# Vocodec_rev2_2.net
KiCad netlist of a schematic drawn in EAGLE
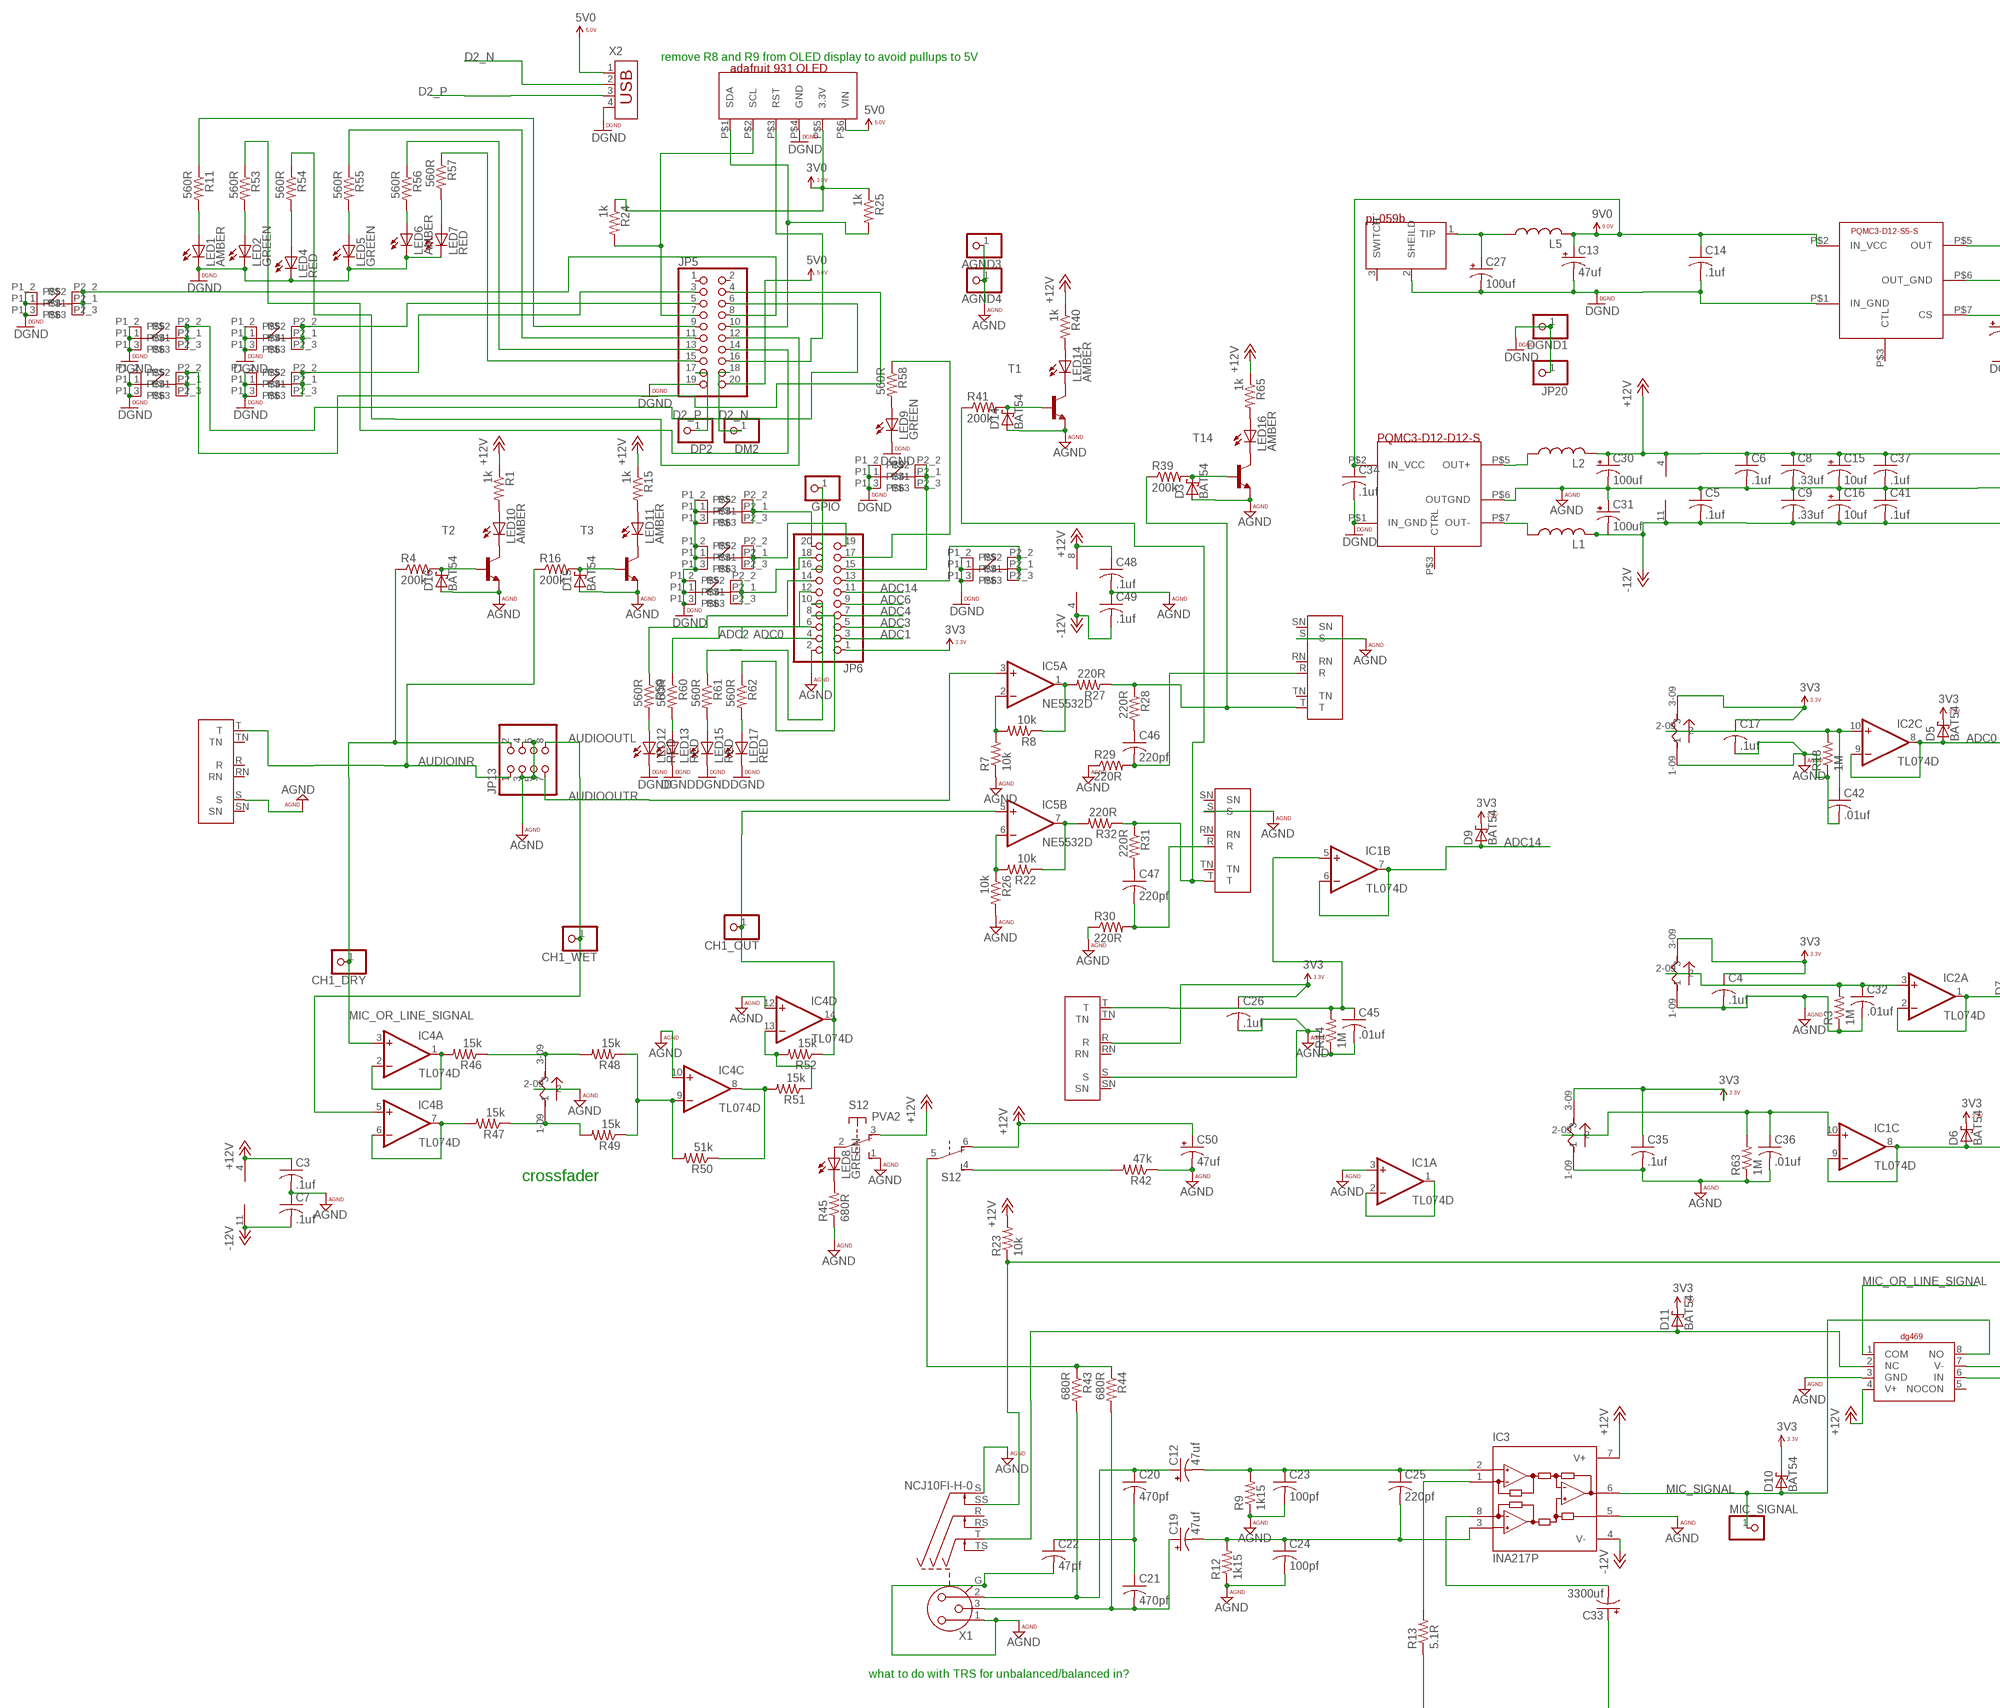
[diagram p0: schematic, sheet 1, part 1 of 3]
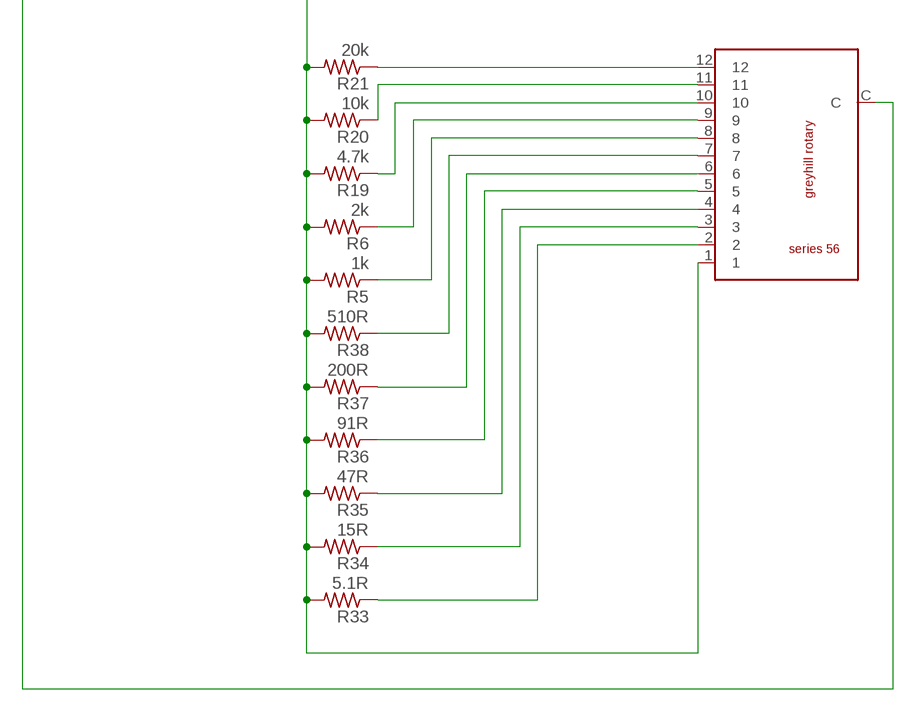
[diagram p1: schematic, sheet 1, part 2 of 3]
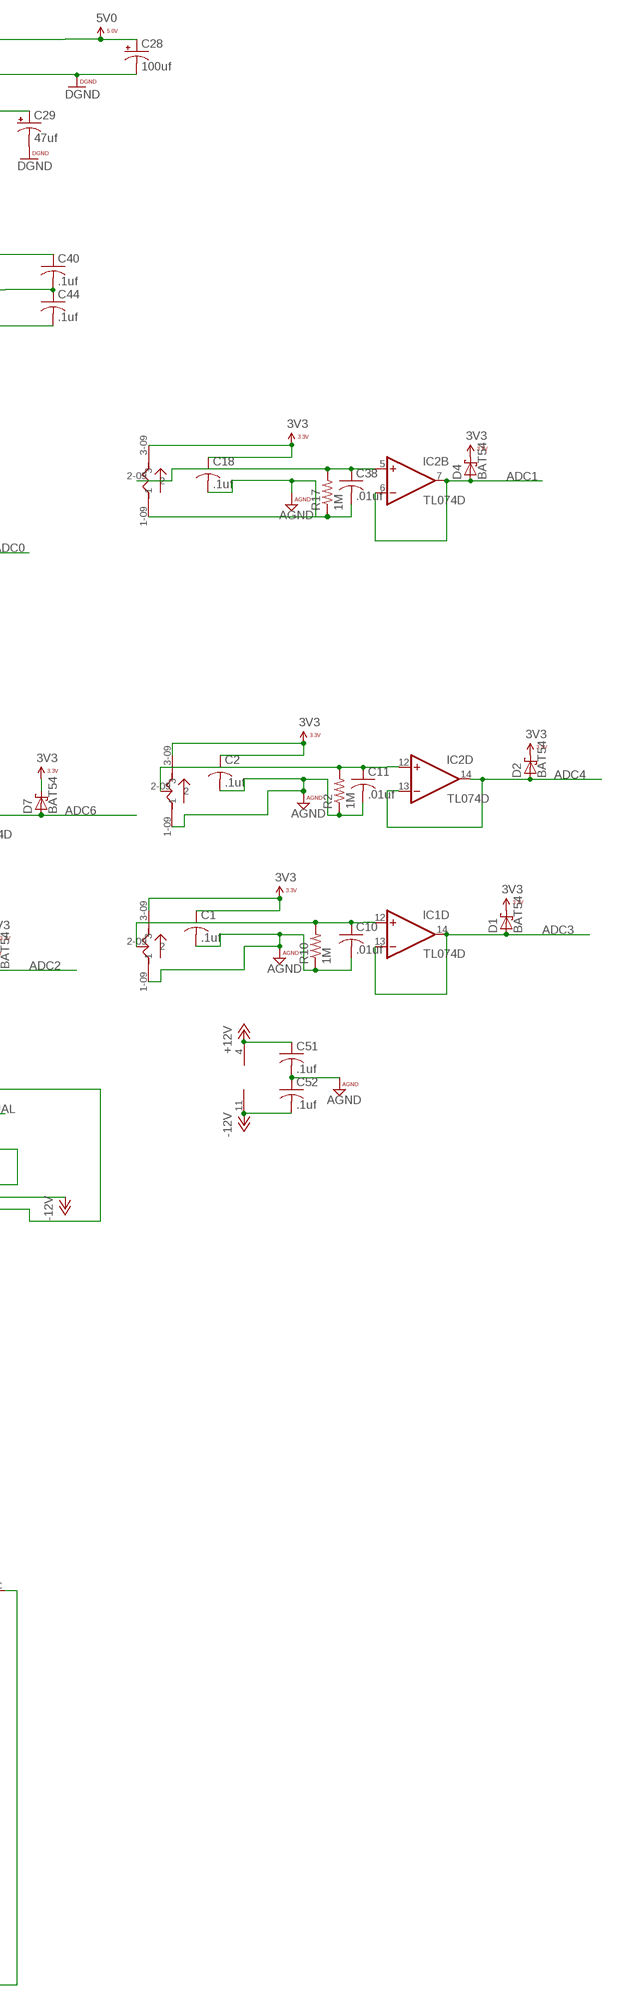
[diagram p2: schematic, sheet 1, part 3 of 3]

(export (version "E")
  (design (tool "Eeschema 10.0.6"))
  (components
    (comp (ref "AGND3")
      (value "PINHD-1X1")
      (footprint "eagle-import:1X01")
      (fields (field (name "PARTNO") "*DNP"))
      (libsource (lib "eagle-import") (part "PINHD-1X1"))
    )
    (comp (ref "AGND4")
      (value "PINHD-1X1")
      (footprint "eagle-import:1X01")
      (fields (field (name "PARTNO") "*DNP"))
      (libsource (lib "eagle-import") (part "PINHD-1X1"))
    )
    (comp (ref "C1")
      (value ".1uf")
      (footprint "eagle-import:C0603")
      (fields (field (name "PARTNO") "CC0603KRX7R8BB104"))
      (libsource (lib "eagle-import") (part "C-USC0603"))
    )
    (comp (ref "C2")
      (value ".1uf")
      (footprint "eagle-import:C0603")
      (fields (field (name "PARTNO") "CC0603KRX7R8BB104"))
      (libsource (lib "eagle-import") (part "C-USC0603"))
    )
    (comp (ref "C3")
      (value ".1uf")
      (footprint "eagle-import:C0603")
      (fields (field (name "PARTNO") "CC0603KRX7R8BB104"))
      (libsource (lib "eagle-import") (part "C-USC0603"))
    )
    (comp (ref "C4")
      (value ".1uf")
      (footprint "eagle-import:C0603")
      (fields (field (name "PARTNO") "CC0603KRX7R8BB104"))
      (libsource (lib "eagle-import") (part "C-USC0603"))
    )
    (comp (ref "C5")
      (value ".1uf")
      (footprint "eagle-import:C0603")
      (fields (field (name "PARTNO") "CC0603KRX7R8BB104"))
      (libsource (lib "eagle-import") (part "C-USC0603"))
    )
    (comp (ref "C6")
      (value ".1uf")
      (footprint "eagle-import:C0603")
      (fields (field (name "PARTNO") "CC0603KRX7R8BB104"))
      (libsource (lib "eagle-import") (part "C-USC0603"))
    )
    (comp (ref "C7")
      (value ".1uf")
      (footprint "eagle-import:C0603")
      (fields (field (name "PARTNO") "CC0603KRX7R8BB104"))
      (libsource (lib "eagle-import") (part "C-USC0603"))
    )
    (comp (ref "C8")
      (value ".33uf")
      (footprint "eagle-import:C0603")
      (fields (field (name "PARTNO") "C1608X7R1H334K080AC"))
      (libsource (lib "eagle-import") (part "C-USC0603"))
    )
    (comp (ref "C9")
      (value ".33uf")
      (footprint "eagle-import:C0603")
      (fields (field (name "PARTNO") "C1608X7R1H334K080AC"))
      (libsource (lib "eagle-import") (part "C-USC0603"))
    )
    (comp (ref "C10")
      (value ".01uf")
      (footprint "eagle-import:C0603")
      (fields (field (name "PARTNO") "CC0603KRX7R8BB103"))
      (libsource (lib "eagle-import") (part "C-USC0603"))
    )
    (comp (ref "C11")
      (value ".01uf")
      (footprint "eagle-import:C0603")
      (fields (field (name "PARTNO") "CC0603KRX7R8BB103"))
      (libsource (lib "eagle-import") (part "C-USC0603"))
    )
    (comp (ref "C12")
      (value "47uf")
      (footprint "eagle-import:PANASONIC_E")
      (fields (field (name "PARTNO") "EEE-1VA470AP"))
      (libsource (lib "eagle-import") (part "CPOL-USE"))
    )
    (comp (ref "C13")
      (value "47uf")
      (footprint "eagle-import:PANASONIC_E")
      (fields (field (name "PARTNO") "EEE-1VA470AP"))
      (libsource (lib "eagle-import") (part "CPOL-USE"))
    )
    (comp (ref "C14")
      (value ".1uf")
      (footprint "eagle-import:C0603")
      (fields (field (name "PARTNO") "CC0603KRX7R8BB104"))
      (libsource (lib "eagle-import") (part "C-USC0603"))
    )
    (comp (ref "C15")
      (value "10uf")
      (footprint "eagle-import:PANASONIC_C")
      (fields (field (name "PARTNO") "EEE-1VA100AR"))
      (libsource (lib "eagle-import") (part "CPOL-USC"))
    )
    (comp (ref "C16")
      (value "10uf")
      (footprint "eagle-import:PANASONIC_C")
      (fields (field (name "PARTNO") "EEE-1VA100AR"))
      (libsource (lib "eagle-import") (part "CPOL-USC"))
    )
    (comp (ref "C17")
      (value ".1uf")
      (footprint "eagle-import:C0603")
      (fields (field (name "PARTNO") "CC0603KRX7R8BB104"))
      (libsource (lib "eagle-import") (part "C-USC0603"))
    )
    (comp (ref "C18")
      (value ".1uf")
      (footprint "eagle-import:C0603")
      (fields (field (name "PARTNO") "CC0603KRX7R8BB104"))
      (libsource (lib "eagle-import") (part "C-USC0603"))
    )
    (comp (ref "C19")
      (value "47uf")
      (footprint "eagle-import:PANASONIC_E")
      (fields (field (name "PARTNO") "EEE-1VA470AP"))
      (libsource (lib "eagle-import") (part "CPOL-USE"))
    )
    (comp (ref "C20")
      (value "470pf")
      (footprint "eagle-import:C0603")
      (fields (field (name "PARTNO") "CC0603JRNPO9BN471"))
      (libsource (lib "eagle-import") (part "C-USC0603"))
    )
    (comp (ref "C21")
      (value "470pf")
      (footprint "eagle-import:C0603")
      (fields (field (name "PARTNO") "CC0603JRNPO9BN471"))
      (libsource (lib "eagle-import") (part "C-USC0603"))
    )
    (comp (ref "C22")
      (value "47pf")
      (footprint "eagle-import:C0603")
      (fields (field (name "PARTNO") "C0603C470J5GACTU"))
      (libsource (lib "eagle-import") (part "C-USC0603"))
    )
    (comp (ref "C23")
      (value "100pf")
      (footprint "eagle-import:C0603")
      (fields (field (name "PARTNO") "C0603C101J3GACTU"))
      (libsource (lib "eagle-import") (part "C-USC0603"))
    )
    (comp (ref "C24")
      (value "100pf")
      (footprint "eagle-import:C0603")
      (fields (field (name "PARTNO") "C0603C101J3GACTU"))
      (libsource (lib "eagle-import") (part "C-USC0603"))
    )
    (comp (ref "C25")
      (value "220pf")
      (footprint "eagle-import:C0603")
      (fields (field (name "PARTNO") "CC0603JRNPO9BN221"))
      (libsource (lib "eagle-import") (part "C-USC0603"))
    )
    (comp (ref "C26")
      (value ".1uf")
      (footprint "eagle-import:C0603")
      (fields (field (name "PARTNO") "CC0603KRX7R8BB104"))
      (libsource (lib "eagle-import") (part "C-USC0603"))
    )
    (comp (ref "C27")
      (value "100uf")
      (footprint "eagle-import:PANASONIC_F")
      (fields (field (name "PARTNO") "EEE-1EA101P"))
      (libsource (lib "eagle-import") (part "CPOL-USF"))
    )
    (comp (ref "C28")
      (value "100uf")
      (footprint "eagle-import:PANASONIC_F")
      (fields (field (name "PARTNO") "EEE-1EA101P"))
      (libsource (lib "eagle-import") (part "CPOL-USF"))
    )
    (comp (ref "C29")
      (value "47uf")
      (footprint "eagle-import:PANASONIC_E")
      (fields (field (name "PARTNO") "EEE-1VA470AP"))
      (libsource (lib "eagle-import") (part "CPOL-USE"))
    )
    (comp (ref "C30")
      (value "100uf")
      (footprint "eagle-import:PANASONIC_F")
      (fields (field (name "PARTNO") "EEE-1EA101P"))
      (libsource (lib "eagle-import") (part "CPOL-USF"))
    )
    (comp (ref "C31")
      (value "100uf")
      (footprint "eagle-import:PANASONIC_F")
      (fields (field (name "PARTNO") "EEE-1EA101P"))
      (libsource (lib "eagle-import") (part "CPOL-USF"))
    )
    (comp (ref "C32")
      (value ".01uf")
      (footprint "eagle-import:C0603")
      (fields (field (name "PARTNO") "CC0603KRX7R8BB103"))
      (libsource (lib "eagle-import") (part "C-USC0603"))
    )
    (comp (ref "C33")
      (value "3300uf")
      (footprint "eagle-import:E5-13")
      (fields (field (name "PARTNO") "EEU-FR1A332"))
      (libsource (lib "eagle-import") (part "CPOL-USE5-13"))
    )
    (comp (ref "C34")
      (value ".1uf")
      (footprint "eagle-import:C0603")
      (fields (field (name "PARTNO") "CC0603KRX7R8BB104"))
      (libsource (lib "eagle-import") (part "C-USC0603"))
    )
    (comp (ref "C35")
      (value ".1uf")
      (footprint "eagle-import:C0603")
      (fields (field (name "PARTNO") "CC0603KRX7R8BB104"))
      (libsource (lib "eagle-import") (part "C-USC0603"))
    )
    (comp (ref "C36")
      (value ".01uf")
      (footprint "eagle-import:C0603")
      (fields (field (name "PARTNO") "CC0603KRX7R8BB103"))
      (libsource (lib "eagle-import") (part "C-USC0603"))
    )
    (comp (ref "C37")
      (value ".1uf")
      (footprint "eagle-import:C0603")
      (fields (field (name "PARTNO") "CC0603KRX7R8BB104"))
      (libsource (lib "eagle-import") (part "C-USC0603"))
    )
    (comp (ref "C38")
      (value ".01uf")
      (footprint "eagle-import:C0603")
      (fields (field (name "PARTNO") "CC0603KRX7R8BB103"))
      (libsource (lib "eagle-import") (part "C-USC0603"))
    )
    (comp (ref "C40")
      (value ".1uf")
      (footprint "eagle-import:C0603")
      (fields (field (name "PARTNO") "CC0603KRX7R8BB104"))
      (libsource (lib "eagle-import") (part "C-USC0603"))
    )
    (comp (ref "C41")
      (value ".1uf")
      (footprint "eagle-import:C0603")
      (fields (field (name "PARTNO") "CC0603KRX7R8BB104"))
      (libsource (lib "eagle-import") (part "C-USC0603"))
    )
    (comp (ref "C42")
      (value ".01uf")
      (footprint "eagle-import:C0603")
      (fields (field (name "PARTNO") "CC0603KRX7R8BB103"))
      (libsource (lib "eagle-import") (part "C-USC0603"))
    )
    (comp (ref "C44")
      (value ".1uf")
      (footprint "eagle-import:C0603")
      (fields (field (name "PARTNO") "CC0603KRX7R8BB104"))
      (libsource (lib "eagle-import") (part "C-USC0603"))
    )
    (comp (ref "C45")
      (value ".01uf")
      (footprint "eagle-import:C0603")
      (fields (field (name "PARTNO") "CC0603KRX7R8BB103"))
      (libsource (lib "eagle-import") (part "C-USC0603"))
    )
    (comp (ref "C46")
      (value "220pf")
      (footprint "eagle-import:C0603")
      (fields (field (name "PARTNO") "CC0603JRNPO9BN221"))
      (libsource (lib "eagle-import") (part "C-USC0603"))
    )
    (comp (ref "C47")
      (value "220pf")
      (footprint "eagle-import:C0603")
      (fields (field (name "PARTNO") "CC0603JRNPO9BN221"))
      (libsource (lib "eagle-import") (part "C-USC0603"))
    )
    (comp (ref "C48")
      (value ".1uf")
      (footprint "eagle-import:C0603")
      (fields (field (name "PARTNO") "CC0603KRX7R8BB104"))
      (libsource (lib "eagle-import") (part "C-USC0603"))
    )
    (comp (ref "C49")
      (value ".1uf")
      (footprint "eagle-import:C0603")
      (fields (field (name "PARTNO") "CC0603KRX7R8BB104"))
      (libsource (lib "eagle-import") (part "C-USC0603"))
    )
    (comp (ref "C50")
      (value "47uf")
      (footprint "eagle-import:PANASONIC_E")
      (fields (field (name "PARTNO") "EEE-1VA470AP"))
      (libsource (lib "eagle-import") (part "CPOL-USE"))
    )
    (comp (ref "C51")
      (value ".1uf")
      (footprint "eagle-import:C0603")
      (fields (field (name "PARTNO") "CC0603KRX7R8BB104"))
      (libsource (lib "eagle-import") (part "C-USC0603"))
    )
    (comp (ref "C52")
      (value ".1uf")
      (footprint "eagle-import:C0603")
      (fields (field (name "PARTNO") "CC0603KRX7R8BB104"))
      (libsource (lib "eagle-import") (part "C-USC0603"))
    )
    (comp (ref "CH1_DRY")
      (value "PINHD-1X1")
      (footprint "eagle-import:1X01")
      (fields (field (name "PARTNO") "*DNP"))
      (libsource (lib "eagle-import") (part "PINHD-1X1"))
    )
    (comp (ref "CH1_OUT")
      (value "PINHD-1X1")
      (footprint "eagle-import:1X01")
      (fields (field (name "PARTNO") "*DNP"))
      (libsource (lib "eagle-import") (part "PINHD-1X1"))
    )
    (comp (ref "CH1_WET")
      (value "PINHD-1X1")
      (footprint "eagle-import:1X01")
      (fields (field (name "PARTNO") "*DNP"))
      (libsource (lib "eagle-import") (part "PINHD-1X1"))
    )
    (comp (ref "D1")
      (value "BAT54")
      (footprint "eagle-import:SOT23")
      (libsource (lib "eagle-import") (part "BAT54"))
    )
    (comp (ref "D2")
      (value "BAT54")
      (footprint "eagle-import:SOT23")
      (libsource (lib "eagle-import") (part "BAT54"))
    )
    (comp (ref "D3")
      (value "BAT54")
      (footprint "eagle-import:SOT23")
      (libsource (lib "eagle-import") (part "BAT54"))
    )
    (comp (ref "D4")
      (value "BAT54")
      (footprint "eagle-import:SOT23")
      (libsource (lib "eagle-import") (part "BAT54"))
    )
    (comp (ref "D5")
      (value "BAT54")
      (footprint "eagle-import:SOT23")
      (libsource (lib "eagle-import") (part "BAT54"))
    )
    (comp (ref "D6")
      (value "BAT54")
      (footprint "eagle-import:SOT23")
      (libsource (lib "eagle-import") (part "BAT54"))
    )
    (comp (ref "D7")
      (value "BAT54")
      (footprint "eagle-import:SOT23")
      (libsource (lib "eagle-import") (part "BAT54"))
    )
    (comp (ref "D9")
      (value "BAT54")
      (footprint "eagle-import:SOT23")
      (libsource (lib "eagle-import") (part "BAT54"))
    )
    (comp (ref "D10")
      (value "BAT54")
      (footprint "eagle-import:SOT23")
      (libsource (lib "eagle-import") (part "BAT54"))
    )
    (comp (ref "D11")
      (value "BAT54")
      (footprint "eagle-import:SOT23")
      (libsource (lib "eagle-import") (part "BAT54"))
    )
    (comp (ref "D14")
      (value "BAT54")
      (footprint "eagle-import:SOT23")
      (libsource (lib "eagle-import") (part "BAT54"))
    )
    (comp (ref "D15")
      (value "BAT54")
      (footprint "eagle-import:SOT23")
      (libsource (lib "eagle-import") (part "BAT54"))
    )
    (comp (ref "D16")
      (value "BAT54")
      (footprint "eagle-import:SOT23")
      (libsource (lib "eagle-import") (part "BAT54"))
    )
    (comp (ref "DGND1")
      (value "PINHD-1X1")
      (footprint "eagle-import:1X01")
      (fields (field (name "PARTNO") "*DNP"))
      (libsource (lib "eagle-import") (part "PINHD-1X1"))
    )
    (comp (ref "DM2")
      (value "PINHD-1X1")
      (footprint "eagle-import:1X01")
      (fields (field (name "PARTNO") "*DNP"))
      (libsource (lib "eagle-import") (part "PINHD-1X1"))
    )
    (comp (ref "DP2")
      (value "PINHD-1X1")
      (footprint "eagle-import:1X01")
      (fields (field (name "PARTNO") "*DNP"))
      (libsource (lib "eagle-import") (part "PINHD-1X1"))
    )
    (comp (ref "GPIO")
      (value "PINHD-1X1")
      (footprint "eagle-import:1X01")
      (fields (field (name "PARTNO") "*DNP"))
      (libsource (lib "eagle-import") (part "PINHD-1X1"))
    )
    (comp (ref "IC1")
      (value "TL074D")
      (footprint "eagle-import:SO14")
      (fields (field (name "PARTNO") "TL074CDR"))
      (libsource (lib "eagle-import") (part "TL074D"))
    )
    (comp (ref "IC2")
      (value "TL074D")
      (footprint "eagle-import:SO14")
      (fields (field (name "PARTNO") "TL074CDR"))
      (libsource (lib "eagle-import") (part "TL074D"))
    )
    (comp (ref "IC3")
      (value "INA217P")
      (footprint "eagle-import:DIL08")
      (fields
        (field (name "MF") "TEXAS INSTRUMENTS")
        (field (name "MPN") "INA217AIP")
        (field (name "PARTNO") "*DNP")
      )
      (libsource (lib "eagle-import") (part "INA217P"))
    )
    (comp (ref "IC4")
      (value "TL074D")
      (footprint "eagle-import:SO14")
      (fields (field (name "PARTNO") "TL074CDR"))
      (libsource (lib "eagle-import") (part "TL074D"))
    )
    (comp (ref "IC5")
      (value "NE5532D")
      (footprint "eagle-import:SO08")
      (fields (field (name "PARTNO") "NE5532DR"))
      (libsource (lib "eagle-import") (part "NE5532D"))
    )
    (comp (ref "IC11")
      (value "PQMC3-D12-D12-S")
      (footprint "eagle-import:PQMC3-D12-D12-S")
      (libsource (lib "eagle-import") (part "PQMC3-D12-D12-S"))
    )
    (comp (ref "IC12")
      (value "PQMC3-D12-S5-S")
      (footprint "eagle-import:PQMC3-D12-D12-S")
      (libsource (lib "eagle-import") (part "PQMC3-D12-S5-S"))
    )
    (comp (ref "IC13")
      (value "DG469")
      (footprint "eagle-import:SO8")
      (fields (field (name "PARTNO") "DG469EY-T1-E3"))
      (libsource (lib "eagle-import") (part "DG469"))
    )
    (comp (ref "J1")
      (value "NRJ6HF2")
      (footprint "eagle-import:NRJ6HF2")
      (fields (field (name "PARTNO") "NRJ6HM-1"))
      (libsource (lib "eagle-import") (part "NRJ6HF2"))
    )
    (comp (ref "J3")
      (value "NRJ6HF2")
      (footprint "eagle-import:NRJ6HF2")
      (fields (field (name "PARTNO") "NRJ6HM-1"))
      (libsource (lib "eagle-import") (part "NRJ6HF2"))
    )
    (comp (ref "J4")
      (value "NRJ6HF2")
      (footprint "eagle-import:NRJ6HF2")
      (fields (field (name "PARTNO") "NRJ6HM-1"))
      (libsource (lib "eagle-import") (part "NRJ6HF2"))
    )
    (comp (ref "J9")
      (value "NRJ6HF2")
      (footprint "eagle-import:NRJ6HF2")
      (fields (field (name "PARTNO") "NRJ6HM-1"))
      (libsource (lib "eagle-import") (part "NRJ6HF2"))
    )
    (comp (ref "J10")
      (value "PJ-059B")
      (footprint "eagle-import:PJ-059B")
      (fields (field (name "PARTNO") "PJ-059A"))
      (libsource (lib "eagle-import") (part "PJ-059B"))
    )
    (comp (ref "JP5")
      (value "PINHD-2X10")
      (footprint "eagle-import:2X10")
      (fields (field (name "PARTNO") "PRPC010DAAN-RC"))
      (libsource (lib "eagle-import") (part "PINHD-2X10"))
    )
    (comp (ref "JP6")
      (value "PINHD-2X10")
      (footprint "eagle-import:2X10")
      (fields (field (name "PARTNO") "PRPC010DAAN-RC"))
      (libsource (lib "eagle-import") (part "PINHD-2X10"))
    )
    (comp (ref "JP13")
      (value "PINHD-2X4")
      (footprint "eagle-import:2X04")
      (fields (field (name "PARTNO") "PRPC004DAAN-RC"))
      (libsource (lib "eagle-import") (part "PINHD-2X4"))
    )
    (comp (ref "JP20")
      (value "PINHD-1X1")
      (footprint "eagle-import:1X01")
      (fields (field (name "PARTNO") "*DNP"))
      (libsource (lib "eagle-import") (part "PINHD-1X1"))
    )
    (comp (ref "L1")
      (value "L-US6000-XXX-RC")
      (footprint "eagle-import:6000-XXXX-RC")
      (fields (field (name "PARTNO") "RLB9012-100KL"))
      (libsource (lib "eagle-import") (part "L-US6000-XXX-RC"))
    )
    (comp (ref "L2")
      (value "L-US6000-XXX-RC")
      (footprint "eagle-import:6000-XXXX-RC")
      (fields (field (name "PARTNO") "RLB9012-100KL"))
      (libsource (lib "eagle-import") (part "L-US6000-XXX-RC"))
    )
    (comp (ref "L5")
      (value "L-US6000-XXX-RC")
      (footprint "eagle-import:6000-XXXX-RC")
      (fields (field (name "PARTNO") "RLB9012-100KL"))
      (libsource (lib "eagle-import") (part "L-US6000-XXX-RC"))
    )
    (comp (ref "LED1")
      (value "AMBER")
      (footprint "eagle-import:PLCC2")
      (fields (field (name "PARTNO") "HSMU-A100-S00J1"))
      (libsource (lib "eagle-import") (part "_T679-?-1E1F1LG"))
    )
    (comp (ref "LED2")
      (value "GREEN")
      (footprint "eagle-import:PLCC2")
      (fields (field (name "PARTNO") "HSMM-A101-R00J1"))
      (libsource (lib "eagle-import") (part "_T679-?-1E1F1LG"))
    )
    (comp (ref "LED4")
      (value "RED")
      (footprint "eagle-import:PLCC2")
      (fields (field (name "PARTNO") "HSMZ-A100-R00J1"))
      (libsource (lib "eagle-import") (part "_T679-?-1E1F1LG"))
    )
    (comp (ref "LED5")
      (value "GREEN")
      (footprint "eagle-import:PLCC2")
      (fields (field (name "PARTNO") "HSMM-A101-R00J1"))
      (libsource (lib "eagle-import") (part "_T679-?-1E1F1LG"))
    )
    (comp (ref "LED6")
      (value "AMBER")
      (footprint "eagle-import:PLCC2")
      (fields (field (name "PARTNO") "HSMU-A100-S00J1"))
      (libsource (lib "eagle-import") (part "_T679-?-1E1F1LG"))
    )
    (comp (ref "LED7")
      (value "RED")
      (footprint "eagle-import:PLCC2")
      (fields (field (name "PARTNO") "HSMZ-A100-R00J1"))
      (libsource (lib "eagle-import") (part "_T679-?-1E1F1LG"))
    )
    (comp (ref "LED8")
      (value "GREEN")
      (footprint "eagle-import:PLCC2")
      (fields (field (name "PARTNO") "HSMM-A101-R00J1"))
      (libsource (lib "eagle-import") (part "_T679-?-1E1F1LG"))
    )
    (comp (ref "LED9")
      (value "GREEN")
      (footprint "eagle-import:PLCC2")
      (fields (field (name "PARTNO") "HSMM-A101-R00J1"))
      (libsource (lib "eagle-import") (part "_T679-?-1E1F1LG"))
    )
    (comp (ref "LED10")
      (value "AMBER")
      (footprint "eagle-import:PLCC2")
      (fields (field (name "PARTNO") "HSMU-A100-S00J1"))
      (libsource (lib "eagle-import") (part "_T679-?-1E1F1LG"))
    )
    (comp (ref "LED11")
      (value "AMBER")
      (footprint "eagle-import:PLCC2")
      (fields (field (name "PARTNO") "HSMU-A100-S00J1"))
      (libsource (lib "eagle-import") (part "_T679-?-1E1F1LG"))
    )
    (comp (ref "LED12")
      (value "RED")
      (footprint "eagle-import:PLCC2")
      (fields (field (name "PARTNO") "HSMZ-A100-R00J1"))
      (libsource (lib "eagle-import") (part "_T679-?-1E1F1LG"))
    )
    (comp (ref "LED13")
      (value "RED")
      (footprint "eagle-import:PLCC2")
      (fields (field (name "PARTNO") "HSMZ-A100-R00J1"))
      (libsource (lib "eagle-import") (part "_T679-?-1E1F1LG"))
    )
    (comp (ref "LED14")
      (value "AMBER")
      (footprint "eagle-import:PLCC2")
      (fields (field (name "PARTNO") "HSMU-A100-S00J1"))
      (libsource (lib "eagle-import") (part "_T679-?-1E1F1LG"))
    )
    (comp (ref "LED15")
      (value "RED")
      (footprint "eagle-import:PLCC2")
      (fields (field (name "PARTNO") "HSMZ-A100-R00J1"))
      (libsource (lib "eagle-import") (part "_T679-?-1E1F1LG"))
    )
    (comp (ref "LED16")
      (value "AMBER")
      (footprint "eagle-import:PLCC2")
      (fields (field (name "PARTNO") "HSMU-A100-S00J1"))
      (libsource (lib "eagle-import") (part "_T679-?-1E1F1LG"))
    )
    (comp (ref "LED17")
      (value "RED")
      (footprint "eagle-import:PLCC2")
      (fields (field (name "PARTNO") "HSMZ-A100-R00J1"))
      (libsource (lib "eagle-import") (part "_T679-?-1E1F1LG"))
    )
    (comp (ref "MIC_SIGNAL")
      (value "PINHD-1X1")
      (footprint "eagle-import:1X01")
      (fields (field (name "PARTNO") "*DNP"))
      (libsource (lib "eagle-import") (part "PINHD-1X1"))
    )
    (comp (ref "OLED1")
      (value "ADAFRUIT_931_OLED_128X32")
      (footprint "eagle-import:ADAFRUIT_128X32_OLED")
      (fields (field (name "PARTNO") "931"))
      (libsource (lib "eagle-import") (part "ADAFRUIT_931_OLED_128X32"))
    )
    (comp (ref "R1")
      (value "1k")
      (footprint "eagle-import:R0603")
      (fields (field (name "PARTNO") "ESR03EZPF1001"))
      (libsource (lib "eagle-import") (part "R-US_R0603"))
    )
    (comp (ref "R2")
      (value "1M")
      (footprint "eagle-import:R0603")
      (fields (field (name "PARTNO") "CRCW06031M00FKEAHP"))
      (libsource (lib "eagle-import") (part "R-US_R0603"))
    )
    (comp (ref "R3")
      (value "1M")
      (footprint "eagle-import:R0603")
      (fields (field (name "PARTNO") "CRCW06031M00FKEAHP"))
      (libsource (lib "eagle-import") (part "R-US_R0603"))
    )
    (comp (ref "R4")
      (value "200k")
      (footprint "eagle-import:R0603")
      (fields (field (name "PARTNO") "ESR03EZPJ204"))
      (libsource (lib "eagle-import") (part "R-US_R0603"))
    )
    (comp (ref "R5")
      (value "1k")
      (footprint "eagle-import:R0603")
      (fields (field (name "PARTNO") "ESR03EZPF1001"))
      (libsource (lib "eagle-import") (part "R-US_R0603"))
    )
    (comp (ref "R6")
      (value "2k")
      (footprint "eagle-import:R0603")
      (fields (field (name "PARTNO") "ERJ-PA3F2001V"))
      (libsource (lib "eagle-import") (part "R-US_R0603"))
    )
    (comp (ref "R7")
      (value "10k")
      (footprint "eagle-import:R0603")
      (fields (field (name "PARTNO") "ESR03EZPF1002"))
      (libsource (lib "eagle-import") (part "R-US_R0603"))
    )
    (comp (ref "R8")
      (value "10k")
      (footprint "eagle-import:R0603")
      (fields (field (name "PARTNO") "ESR03EZPF1002"))
      (libsource (lib "eagle-import") (part "R-US_R0603"))
    )
    (comp (ref "R9")
      (value "1k15")
      (footprint "eagle-import:R0603")
      (fields (field (name "PARTNO") "ERA-3AEB1151V"))
      (libsource (lib "eagle-import") (part "R-US_R0603"))
    )
    (comp (ref "R10")
      (value "1M")
      (footprint "eagle-import:R0603")
      (fields (field (name "PARTNO") "CRCW06031M00FKEAHP"))
      (libsource (lib "eagle-import") (part "R-US_R0603"))
    )
    (comp (ref "R11")
      (value "560R")
      (footprint "eagle-import:R0603")
      (fields (field (name "PARTNO") "ESR03EZPF5600"))
      (libsource (lib "eagle-import") (part "R-US_R0603"))
    )
    (comp (ref "R12")
      (value "1k15")
      (footprint "eagle-import:R0603")
      (fields (field (name "PARTNO") "ERA-3AEB1151V"))
      (libsource (lib "eagle-import") (part "R-US_R0603"))
    )
    (comp (ref "R13")
      (value "5.1R")
      (footprint "eagle-import:R0603")
      (fields (field (name "PARTNO") "RC0603JR-075R1L"))
      (libsource (lib "eagle-import") (part "R-US_R0603"))
    )
    (comp (ref "R14")
      (value "1M")
      (footprint "eagle-import:R0603")
      (fields (field (name "PARTNO") "CRCW06031M00FKEAHP"))
      (libsource (lib "eagle-import") (part "R-US_R0603"))
    )
    (comp (ref "R15")
      (value "1k")
      (footprint "eagle-import:R0603")
      (fields (field (name "PARTNO") "ESR03EZPF1001"))
      (libsource (lib "eagle-import") (part "R-US_R0603"))
    )
    (comp (ref "R16")
      (value "200k")
      (footprint "eagle-import:R0603")
      (fields (field (name "PARTNO") "ESR03EZPJ204"))
      (libsource (lib "eagle-import") (part "R-US_R0603"))
    )
    (comp (ref "R17")
      (value "1M")
      (footprint "eagle-import:R0603")
      (fields (field (name "PARTNO") "CRCW06031M00FKEAHP"))
      (libsource (lib "eagle-import") (part "R-US_R0603"))
    )
    (comp (ref "R18")
      (value "1M")
      (footprint "eagle-import:R0603")
      (fields (field (name "PARTNO") "CRCW06031M00FKEAHP"))
      (libsource (lib "eagle-import") (part "R-US_R0603"))
    )
    (comp (ref "R19")
      (value "4.7k")
      (footprint "eagle-import:R0603")
      (fields (field (name "PARTNO") "CRCW06034K70FKEAHP"))
      (libsource (lib "eagle-import") (part "R-US_R0603"))
    )
    (comp (ref "R20")
      (value "10k")
      (footprint "eagle-import:R0603")
      (fields (field (name "PARTNO") "ESR03EZPF1002"))
      (libsource (lib "eagle-import") (part "R-US_R0603"))
    )
    (comp (ref "R21")
      (value "20k")
      (footprint "eagle-import:R0603")
      (fields (field (name "PARTNO") "ESR03EZPF2002"))
      (libsource (lib "eagle-import") (part "R-US_R0603"))
    )
    (comp (ref "R22")
      (value "10k")
      (footprint "eagle-import:R0603")
      (fields (field (name "PARTNO") "ESR03EZPF1002"))
      (libsource (lib "eagle-import") (part "R-US_R0603"))
    )
    (comp (ref "R23")
      (value "10k")
      (footprint "eagle-import:R0603")
      (fields (field (name "PARTNO") "ESR03EZPF1002"))
      (libsource (lib "eagle-import") (part "R-US_R0603"))
    )
    (comp (ref "R24")
      (value "1k")
      (footprint "eagle-import:R0603")
      (fields (field (name "PARTNO") "ESR03EZPF1001"))
      (libsource (lib "eagle-import") (part "R-US_R0603"))
    )
    (comp (ref "R25")
      (value "1k")
      (footprint "eagle-import:R0603")
      (fields (field (name "PARTNO") "ESR03EZPF1001"))
      (libsource (lib "eagle-import") (part "R-US_R0603"))
    )
    (comp (ref "R26")
      (value "10k")
      (footprint "eagle-import:R0603")
      (fields (field (name "PARTNO") "ESR03EZPF1002"))
      (libsource (lib "eagle-import") (part "R-US_R0603"))
    )
    (comp (ref "R27")
      (value "220R")
      (footprint "eagle-import:R0603")
      (fields (field (name "PARTNO") "ESR03EZPJ221"))
      (libsource (lib "eagle-import") (part "R-US_R0603"))
    )
    (comp (ref "R28")
      (value "220R")
      (footprint "eagle-import:R0603")
      (fields (field (name "PARTNO") "ESR03EZPJ221"))
      (libsource (lib "eagle-import") (part "R-US_R0603"))
    )
    (comp (ref "R29")
      (value "220R")
      (footprint "eagle-import:R0603")
      (fields (field (name "PARTNO") "ESR03EZPJ221"))
      (libsource (lib "eagle-import") (part "R-US_R0603"))
    )
    (comp (ref "R30")
      (value "220R")
      (footprint "eagle-import:R0603")
      (fields (field (name "PARTNO") "ESR03EZPJ221"))
      (libsource (lib "eagle-import") (part "R-US_R0603"))
    )
    (comp (ref "R31")
      (value "220R")
      (footprint "eagle-import:R0603")
      (fields (field (name "PARTNO") "ESR03EZPJ221"))
      (libsource (lib "eagle-import") (part "R-US_R0603"))
    )
    (comp (ref "R32")
      (value "220R")
      (footprint "eagle-import:R0603")
      (fields (field (name "PARTNO") "ESR03EZPJ221"))
      (libsource (lib "eagle-import") (part "R-US_R0603"))
    )
    (comp (ref "R33")
      (value "5.1R")
      (footprint "eagle-import:R0603")
      (fields (field (name "PARTNO") "RC0603JR-075R1L"))
      (libsource (lib "eagle-import") (part "R-US_R0603"))
    )
    (comp (ref "R34")
      (value "15R")
      (footprint "eagle-import:R0603")
      (fields (field (name "PARTNO") "RC0603JR-0715RL"))
      (libsource (lib "eagle-import") (part "R-US_R0603"))
    )
    (comp (ref "R35")
      (value "47R")
      (footprint "eagle-import:R0603")
      (fields (field (name "PARTNO") "RC0603JR-0747RL"))
      (libsource (lib "eagle-import") (part "R-US_R0603"))
    )
    (comp (ref "R36")
      (value "91R")
      (footprint "eagle-import:R0603")
      (fields (field (name "PARTNO") "RC0603JR-0791RL"))
      (libsource (lib "eagle-import") (part "R-US_R0603"))
    )
    (comp (ref "R37")
      (value "200R")
      (footprint "eagle-import:R0603")
      (fields (field (name "PARTNO") "RC0603JR-07200RL"))
      (libsource (lib "eagle-import") (part "R-US_R0603"))
    )
    (comp (ref "R38")
      (value "510R")
      (footprint "eagle-import:R0603")
      (fields (field (name "PARTNO") "RC0603JR-07510RL"))
      (libsource (lib "eagle-import") (part "R-US_R0603"))
    )
    (comp (ref "R39")
      (value "200k")
      (footprint "eagle-import:R0603")
      (fields (field (name "PARTNO") "ESR03EZPJ204"))
      (libsource (lib "eagle-import") (part "R-US_R0603"))
    )
    (comp (ref "R40")
      (value "1k")
      (footprint "eagle-import:R0603")
      (fields (field (name "PARTNO") "ESR03EZPF1001"))
      (libsource (lib "eagle-import") (part "R-US_R0603"))
    )
    (comp (ref "R41")
      (value "200k")
      (footprint "eagle-import:R0603")
      (fields (field (name "PARTNO") "ESR03EZPJ204"))
      (libsource (lib "eagle-import") (part "R-US_R0603"))
    )
    (comp (ref "R42")
      (value "47k")
      (footprint "eagle-import:R0603")
      (fields (field (name "PARTNO") "ESR03EZPJ473"))
      (libsource (lib "eagle-import") (part "R-US_R0603"))
    )
    (comp (ref "R43")
      (value "680R")
      (footprint "eagle-import:R0603")
      (fields (field (name "PARTNO") "CRCW0603680RJNEAHP"))
      (libsource (lib "eagle-import") (part "R-US_R0603"))
    )
    (comp (ref "R44")
      (value "680R")
      (footprint "eagle-import:R0603")
      (fields (field (name "PARTNO") "CRCW0603680RJNEAHP"))
      (libsource (lib "eagle-import") (part "R-US_R0603"))
    )
    (comp (ref "R45")
      (value "680R")
      (footprint "eagle-import:R0603")
      (fields (field (name "PARTNO") "CRCW0603680RJNEAHP"))
      (libsource (lib "eagle-import") (part "R-US_R0603"))
    )
    (comp (ref "R46")
      (value "15k")
      (footprint "eagle-import:R0603")
      (fields (field (name "PARTNO") "ESR03EZPF1502"))
      (libsource (lib "eagle-import") (part "R-US_R0603"))
    )
    (comp (ref "R47")
      (value "15k")
      (footprint "eagle-import:R0603")
      (fields (field (name "PARTNO") "ESR03EZPF1502"))
      (libsource (lib "eagle-import") (part "R-US_R0603"))
    )
    (comp (ref "R48")
      (value "15k")
      (footprint "eagle-import:R0603")
      (fields (field (name "PARTNO") "ESR03EZPF1502"))
      (libsource (lib "eagle-import") (part "R-US_R0603"))
    )
    (comp (ref "R49")
      (value "15k")
      (footprint "eagle-import:R0603")
      (fields (field (name "PARTNO") "ESR03EZPF1502"))
      (libsource (lib "eagle-import") (part "R-US_R0603"))
    )
    (comp (ref "R50")
      (value "51k")
      (footprint "eagle-import:R0603")
      (fields (field (name "PARTNO") "ERJ-PA3F5102V"))
      (libsource (lib "eagle-import") (part "R-US_R0603"))
    )
    (comp (ref "R51")
      (value "15k")
      (footprint "eagle-import:R0603")
      (fields (field (name "PARTNO") "ESR03EZPF1502"))
      (libsource (lib "eagle-import") (part "R-US_R0603"))
    )
    (comp (ref "R52")
      (value "15k")
      (footprint "eagle-import:R0603")
      (fields (field (name "PARTNO") "ESR03EZPF1502"))
      (libsource (lib "eagle-import") (part "R-US_R0603"))
    )
    (comp (ref "R53")
      (value "560R")
      (footprint "eagle-import:R0603")
      (fields (field (name "PARTNO") "ESR03EZPF5600"))
      (libsource (lib "eagle-import") (part "R-US_R0603"))
    )
    (comp (ref "R54")
      (value "560R")
      (footprint "eagle-import:R0603")
      (fields (field (name "PARTNO") "ESR03EZPF5600"))
      (libsource (lib "eagle-import") (part "R-US_R0603"))
    )
    (comp (ref "R55")
      (value "560R")
      (footprint "eagle-import:R0603")
      (fields (field (name "PARTNO") "ESR03EZPF5600"))
      (libsource (lib "eagle-import") (part "R-US_R0603"))
    )
    (comp (ref "R56")
      (value "560R")
      (footprint "eagle-import:R0603")
      (fields (field (name "PARTNO") "ESR03EZPF5600"))
      (libsource (lib "eagle-import") (part "R-US_R0603"))
    )
    (comp (ref "R57")
      (value "560R")
      (footprint "eagle-import:R0603")
      (fields (field (name "PARTNO") "ESR03EZPF5600"))
      (libsource (lib "eagle-import") (part "R-US_R0603"))
    )
    (comp (ref "R58")
      (value "560R")
      (footprint "eagle-import:R0603")
      (fields (field (name "PARTNO") "ESR03EZPF5600"))
      (libsource (lib "eagle-import") (part "R-US_R0603"))
    )
    (comp (ref "R59")
      (value "560R")
      (footprint "eagle-import:R0603")
      (fields (field (name "PARTNO") "ESR03EZPF5600"))
      (libsource (lib "eagle-import") (part "R-US_R0603"))
    )
    (comp (ref "R60")
      (value "560R")
      (footprint "eagle-import:R0603")
      (fields (field (name "PARTNO") "ESR03EZPF5600"))
      (libsource (lib "eagle-import") (part "R-US_R0603"))
    )
    (comp (ref "R61")
      (value "560R")
      (footprint "eagle-import:R0603")
      (fields (field (name "PARTNO") "ESR03EZPF5600"))
      (libsource (lib "eagle-import") (part "R-US_R0603"))
    )
    (comp (ref "R62")
      (value "560R")
      (footprint "eagle-import:R0603")
      (fields (field (name "PARTNO") "ESR03EZPF5600"))
      (libsource (lib "eagle-import") (part "R-US_R0603"))
    )
    (comp (ref "R63")
      (value "1M")
      (footprint "eagle-import:R0603")
      (fields (field (name "PARTNO") "CRCW06031M00FKEAHP"))
      (libsource (lib "eagle-import") (part "R-US_R0603"))
    )
    (comp (ref "R65")
      (value "1k")
      (footprint "eagle-import:R0603")
      (fields (field (name "PARTNO") "ESR03EZPF1001"))
      (libsource (lib "eagle-import") (part "R-US_R0603"))
    )
    (comp (ref "S12")
      (value "PVA2")
      (footprint "eagle-import:PVA2F")
      (fields (field (name "PARTNO") "PVA2 OA H4 1.7N V2"))
      (libsource (lib "eagle-import") (part "PVA2"))
    )
    (comp (ref "T1")
      (value "MMBT3904LT1-NPN-SOT23-BEC")
      (footprint "eagle-import:SOT23-BEC")
      (fields (field (name "PARTNO") "MMBT3904-TP"))
      (libsource (lib "eagle-import") (part "-NPN-SOT23-BECMMBT3904LT1"))
    )
    (comp (ref "T2")
      (value "MMBT3904LT1-NPN-SOT23-BEC")
      (footprint "eagle-import:SOT23-BEC")
      (fields (field (name "PARTNO") "MMBT3904-TP"))
      (libsource (lib "eagle-import") (part "-NPN-SOT23-BECMMBT3904LT1"))
    )
    (comp (ref "T3")
      (value "MMBT3904LT1-NPN-SOT23-BEC")
      (footprint "eagle-import:SOT23-BEC")
      (fields (field (name "PARTNO") "MMBT3904-TP"))
      (libsource (lib "eagle-import") (part "-NPN-SOT23-BECMMBT3904LT1"))
    )
    (comp (ref "T14")
      (value "MMBT3904LT1-NPN-SOT23-BEC")
      (footprint "eagle-import:SOT23-BEC")
      (fields (field (name "PARTNO") "MMBT3904-TP"))
      (libsource (lib "eagle-import") (part "-NPN-SOT23-BECMMBT3904LT1"))
    )
    (comp (ref "U$1")
      (value "56DP30")
      (footprint "eagle-import:56DP30")
      (fields (field (name "PARTNO") "56DP30-01-1-AJN"))
      (libsource (lib "eagle-import") (part "56DP30"))
    )
    (comp (ref "U$7")
      (value "TL52_PLUS")
      (footprint "eagle-import:TL52_PLUS")
      (fields (field (name "PARTNO") "*DNP"))
      (libsource (lib "eagle-import") (part "TL52_PLUS"))
    )
    (comp (ref "U$11")
      (value "TL52_PLUS")
      (footprint "eagle-import:TL52_PLUS")
      (fields (field (name "PARTNO") "*DNP"))
      (libsource (lib "eagle-import") (part "TL52_PLUS"))
    )
    (comp (ref "U$12")
      (value "RK09")
      (footprint "eagle-import:RK09")
      (fields (field (name "PARTNO") "*DNP"))
      (libsource (lib "eagle-import") (part "RK09"))
    )
    (comp (ref "U$14")
      (value "RK09")
      (footprint "eagle-import:RK09")
      (fields (field (name "PARTNO") "*DNP"))
      (libsource (lib "eagle-import") (part "RK09"))
    )
    (comp (ref "U$16")
      (value "RK09")
      (footprint "eagle-import:RK09")
      (fields (field (name "PARTNO") "*DNP"))
      (libsource (lib "eagle-import") (part "RK09"))
    )
    (comp (ref "U$27")
      (value "RK09")
      (footprint "eagle-import:RK09")
      (fields (field (name "PARTNO") "*DNP"))
      (libsource (lib "eagle-import") (part "RK09"))
    )
    (comp (ref "U$28")
      (value "RK09")
      (footprint "eagle-import:RK09")
      (fields (field (name "PARTNO") "*DNP"))
      (libsource (lib "eagle-import") (part "RK09"))
    )
    (comp (ref "U$31")
      (value "RK09")
      (footprint "eagle-import:RK09")
      (fields (field (name "PARTNO") "*DNP"))
      (libsource (lib "eagle-import") (part "RK09"))
    )
    (comp (ref "U$32")
      (value "RK09")
      (footprint "eagle-import:RK09")
      (fields (field (name "PARTNO") "*DNP"))
      (libsource (lib "eagle-import") (part "RK09"))
    )
    (comp (ref "U$33")
      (value "TL52_PLUS")
      (footprint "eagle-import:TL52_PLUS")
      (fields (field (name "PARTNO") "*DNP"))
      (libsource (lib "eagle-import") (part "TL52_PLUS"))
    )
    (comp (ref "U$39")
      (value "TL52_PLUS")
      (footprint "eagle-import:TL52_PLUS")
      (fields (field (name "PARTNO") "*DNP"))
      (libsource (lib "eagle-import") (part "TL52_PLUS"))
    )
    (comp (ref "U$40")
      (value "TL52_PLUS")
      (footprint "eagle-import:TL52_PLUS")
      (fields (field (name "PARTNO") "*DNP"))
      (libsource (lib "eagle-import") (part "TL52_PLUS"))
    )
    (comp (ref "U$42")
      (value "TL52_PLUS")
      (footprint "eagle-import:TL52_PLUS")
      (fields (field (name "PARTNO") "*DNP"))
      (libsource (lib "eagle-import") (part "TL52_PLUS"))
    )
    (comp (ref "U$43")
      (value "TL52_PLUS")
      (footprint "eagle-import:TL52_PLUS")
      (fields (field (name "PARTNO") "*DNP"))
      (libsource (lib "eagle-import") (part "TL52_PLUS"))
    )
    (comp (ref "U$44")
      (value "TL52_PLUS")
      (footprint "eagle-import:TL52_PLUS")
      (fields (field (name "PARTNO") "*DNP"))
      (libsource (lib "eagle-import") (part "TL52_PLUS"))
    )
    (comp (ref "U$45")
      (value "TL52_PLUS")
      (footprint "eagle-import:TL52_PLUS")
      (fields (field (name "PARTNO") "*DNP"))
      (libsource (lib "eagle-import") (part "TL52_PLUS"))
    )
    (comp (ref "U$48")
      (value "TL52_PLUS")
      (footprint "eagle-import:TL52_PLUS")
      (fields (field (name "PARTNO") "*DNP"))
      (libsource (lib "eagle-import") (part "TL52_PLUS"))
    )
    (comp (ref "X1")
      (value "NCJ10FI-H-0")
      (footprint "eagle-import:NCJ10FI-H-0")
      (fields (field (name "PARTNO") "NCJ10FI-H-01"))
      (libsource (lib "eagle-import") (part "NCJ10FI-H-0"))
    )
    (comp (ref "X2")
      (value "USB-787616")
      (footprint "eagle-import:USB")
      (fields (field (name "PARTNO") "292303-1"))
      (libsource (lib "eagle-import") (part "USB-787616"))
    )
  )
  (nets
    (net (code "1") (name "+12V") (class "Default")
      (node (ref "C15") (pin "+") (pinfunction "+_+") (pintype "passive"))
      (node (ref "C3") (pin "1") (pinfunction "1_1") (pintype "passive"))
      (node (ref "C30") (pin "+") (pinfunction "+_+") (pintype "passive"))
      (node (ref "C37") (pin "1") (pinfunction "1_1") (pintype "passive"))
      (node (ref "C40") (pin "1") (pinfunction "1_1") (pintype "passive"))
      (node (ref "C48") (pin "1") (pinfunction "1_1") (pintype "passive"))
      (node (ref "C50") (pin "+") (pinfunction "+_+") (pintype "passive"))
      (node (ref "C51") (pin "1") (pinfunction "1_1") (pintype "passive"))
      (node (ref "C6") (pin "1") (pinfunction "1_1") (pintype "passive"))
      (node (ref "C8") (pin "1") (pinfunction "1_1") (pintype "passive"))
      (node (ref "IC1") (pin "4") (pinfunction "V+_4") (pintype "power_in"))
      (node (ref "IC13") (pin "4") (pinfunction "V+_4") (pintype "bidirectional"))
      (node (ref "IC2") (pin "4") (pinfunction "V+_4") (pintype "power_in"))
      (node (ref "IC3") (pin "7") (pinfunction "V+_7") (pintype "power_in"))
      (node (ref "IC4") (pin "4") (pinfunction "V+_4") (pintype "power_in"))
      (node (ref "IC5") (pin "8") (pinfunction "V+_8") (pintype "power_in"))
      (node (ref "L2") (pin "2") (pinfunction "2_2") (pintype "passive"))
      (node (ref "R1") (pin "1") (pinfunction "1_1") (pintype "passive"))
      (node (ref "R15") (pin "1") (pinfunction "1_1") (pintype "passive"))
      (node (ref "R23") (pin "2") (pinfunction "2_2") (pintype "passive"))
      (node (ref "R40") (pin "1") (pinfunction "1_1") (pintype "passive"))
      (node (ref "R65") (pin "1") (pinfunction "1_1") (pintype "passive"))
      (node (ref "S12") (pin "3") (pinfunction "O_3") (pintype "passive"))
      (node (ref "S12") (pin "6") (pinfunction "O_6") (pintype "passive"))
    )
    (net (code "2") (name "-12V") (class "Default")
      (node (ref "C16") (pin "-") (pinfunction "-_-") (pintype "passive"))
      (node (ref "C31") (pin "-") (pinfunction "-_-") (pintype "passive"))
      (node (ref "C41") (pin "2") (pinfunction "2_2") (pintype "passive"))
      (node (ref "C44") (pin "2") (pinfunction "2_2") (pintype "passive"))
      (node (ref "C49") (pin "2") (pinfunction "2_2") (pintype "passive"))
      (node (ref "C5") (pin "2") (pinfunction "2_2") (pintype "passive"))
      (node (ref "C52") (pin "2") (pinfunction "2_2") (pintype "passive"))
      (node (ref "C7") (pin "2") (pinfunction "2_2") (pintype "passive"))
      (node (ref "C9") (pin "2") (pinfunction "2_2") (pintype "passive"))
      (node (ref "IC1") (pin "11") (pinfunction "V-_11") (pintype "power_in"))
      (node (ref "IC13") (pin "7") (pinfunction "V-_7") (pintype "bidirectional"))
      (node (ref "IC2") (pin "11") (pinfunction "V-_11") (pintype "power_in"))
      (node (ref "IC3") (pin "4") (pinfunction "V-_4") (pintype "power_in"))
      (node (ref "IC4") (pin "11") (pinfunction "V-_11") (pintype "power_in"))
      (node (ref "IC5") (pin "4") (pinfunction "V-_4") (pintype "power_in"))
      (node (ref "L1") (pin "2") (pinfunction "2_2") (pintype "passive"))
    )
    (net (code "3") (name "/ADC0") (class "Default")
      (node (ref "D5") (pin "1") (pinfunction "A_1") (pintype "passive"))
      (node (ref "IC2") (pin "8") (pinfunction "OUT_8") (pintype "output"))
      (node (ref "IC2") (pin "9") (pinfunction "-IN_9") (pintype "input"))
      (node (ref "JP6") (pin "4") (pinfunction "4_4") (pintype "passive"))
    )
    (net (code "4") (name "/ADC1") (class "Default")
      (node (ref "D4") (pin "1") (pinfunction "A_1") (pintype "passive"))
      (node (ref "IC2") (pin "6") (pinfunction "-IN_6") (pintype "input"))
      (node (ref "IC2") (pin "7") (pinfunction "OUT_7") (pintype "output"))
      (node (ref "JP6") (pin "3") (pinfunction "3_3") (pintype "passive"))
    )
    (net (code "5") (name "/ADC2") (class "Default")
      (node (ref "D6") (pin "1") (pinfunction "A_1") (pintype "passive"))
      (node (ref "IC1") (pin "8") (pinfunction "OUT_8") (pintype "output"))
      (node (ref "IC1") (pin "9") (pinfunction "-IN_9") (pintype "input"))
      (node (ref "JP6") (pin "6") (pinfunction "6_6") (pintype "passive"))
    )
    (net (code "6") (name "/ADC3") (class "Default")
      (node (ref "D1") (pin "1") (pinfunction "A_1") (pintype "passive"))
      (node (ref "IC1") (pin "13") (pinfunction "-IN_13") (pintype "input"))
      (node (ref "IC1") (pin "14") (pinfunction "OUT_14") (pintype "output"))
      (node (ref "JP6") (pin "5") (pinfunction "5_5") (pintype "passive"))
    )
    (net (code "7") (name "/ADC4") (class "Default")
      (node (ref "D2") (pin "1") (pinfunction "A_1") (pintype "passive"))
      (node (ref "IC2") (pin "13") (pinfunction "-IN_13") (pintype "input"))
      (node (ref "IC2") (pin "14") (pinfunction "OUT_14") (pintype "output"))
      (node (ref "JP6") (pin "7") (pinfunction "7_7") (pintype "passive"))
    )
    (net (code "8") (name "/ADC6") (class "Default")
      (node (ref "D7") (pin "1") (pinfunction "A_1") (pintype "passive"))
      (node (ref "IC2") (pin "1") (pinfunction "OUT_1") (pintype "output"))
      (node (ref "IC2") (pin "2") (pinfunction "-IN_2") (pintype "input"))
      (node (ref "JP6") (pin "9") (pinfunction "9_9") (pintype "passive"))
    )
    (net (code "9") (name "/ADC14") (class "Default")
      (node (ref "D9") (pin "1") (pinfunction "A_1") (pintype "passive"))
      (node (ref "IC1") (pin "6") (pinfunction "-IN_6") (pintype "input"))
      (node (ref "IC1") (pin "7") (pinfunction "OUT_7") (pintype "output"))
      (node (ref "JP6") (pin "11") (pinfunction "11_11") (pintype "passive"))
    )
    (net (code "10") (name "/AUDIOINR") (class "Default")
      (node (ref "J1") (pin "T") (pinfunction "T_T") (pintype "bidirectional"))
      (node (ref "JP13") (pin "1") (pinfunction "1_1") (pintype "passive"))
      (node (ref "R16") (pin "1") (pinfunction "1_1") (pintype "passive"))
    )
    (net (code "11") (name "/AUDIOOUTL") (class "Default")
      (node (ref "CH1_WET") (pin "1") (pinfunction "1_1") (pintype "passive"))
      (node (ref "IC4") (pin "5") (pinfunction "+IN_5") (pintype "input"))
      (node (ref "JP13") (pin "8") (pinfunction "8_8") (pintype "passive"))
    )
    (net (code "12") (name "/AUDIOOUTR") (class "Default")
      (node (ref "IC5") (pin "3") (pinfunction "+IN_3") (pintype "input"))
      (node (ref "JP13") (pin "7") (pinfunction "7_7") (pintype "passive"))
    )
    (net (code "13") (name "/D2_N") (class "Default")
      (node (ref "DM2") (pin "1") (pinfunction "1_1") (pintype "passive"))
      (node (ref "JP5") (pin "18") (pinfunction "18_18") (pintype "passive"))
      (node (ref "X2") (pin "2") (pinfunction "2_2") (pintype "passive"))
    )
    (net (code "14") (name "/D2_P") (class "Default")
      (node (ref "DP2") (pin "1") (pinfunction "1_1") (pintype "passive"))
      (node (ref "JP5") (pin "17") (pinfunction "17_17") (pintype "passive"))
      (node (ref "X2") (pin "3") (pinfunction "3_3") (pintype "passive"))
    )
    (net (code "15") (name "/MIC_OR_LINE_SIGNAL") (class "Default")
      (node (ref "CH1_DRY") (pin "1") (pinfunction "1_1") (pintype "passive"))
      (node (ref "IC13") (pin "1") (pinfunction "COM_1") (pintype "bidirectional"))
      (node (ref "IC4") (pin "3") (pinfunction "+IN_3") (pintype "input"))
      (node (ref "JP13") (pin "2") (pinfunction "2_2") (pintype "passive"))
      (node (ref "R4") (pin "1") (pinfunction "1_1") (pintype "passive"))
    )
    (net (code "16") (name "/MIC_SIGNAL") (class "Default")
      (node (ref "D10") (pin "1") (pinfunction "A_1") (pintype "passive"))
      (node (ref "IC13") (pin "8") (pinfunction "NO_8") (pintype "bidirectional"))
      (node (ref "IC3") (pin "6") (pinfunction "OUT_6") (pintype "output"))
      (node (ref "MIC_SIGNAL") (pin "1") (pinfunction "1_1") (pintype "passive"))
    )
    (net (code "17") (name "3V0") (class "Default")
      (node (ref "OLED1") (pin "P$5") (pinfunction "3.3V_P$5") (pintype "bidirectional"))
      (node (ref "R24") (pin "1") (pinfunction "1_1") (pintype "passive"))
      (node (ref "R25") (pin "1") (pinfunction "1_1") (pintype "passive"))
    )
    (net (code "18") (name "3V3") (class "Default")
      (node (ref "C1") (pin "1") (pinfunction "1_1") (pintype "passive"))
      (node (ref "C17") (pin "1") (pinfunction "1_1") (pintype "passive"))
      (node (ref "C18") (pin "1") (pinfunction "1_1") (pintype "passive"))
      (node (ref "C2") (pin "1") (pinfunction "1_1") (pintype "passive"))
      (node (ref "C26") (pin "1") (pinfunction "1_1") (pintype "passive"))
      (node (ref "C35") (pin "1") (pinfunction "1_1") (pintype "passive"))
      (node (ref "C4") (pin "1") (pinfunction "1_1") (pintype "passive"))
      (node (ref "D1") (pin "3") (pinfunction "C_3") (pintype "passive"))
      (node (ref "D10") (pin "3") (pinfunction "C_3") (pintype "passive"))
      (node (ref "D11") (pin "3") (pinfunction "C_3") (pintype "passive"))
      (node (ref "D2") (pin "3") (pinfunction "C_3") (pintype "passive"))
      (node (ref "D4") (pin "3") (pinfunction "C_3") (pintype "passive"))
      (node (ref "D5") (pin "3") (pinfunction "C_3") (pintype "passive"))
      (node (ref "D6") (pin "3") (pinfunction "C_3") (pintype "passive"))
      (node (ref "D7") (pin "3") (pinfunction "C_3") (pintype "passive"))
      (node (ref "D9") (pin "3") (pinfunction "C_3") (pintype "passive"))
      (node (ref "J9") (pin "R") (pinfunction "R_R") (pintype "bidirectional"))
      (node (ref "JP6") (pin "1") (pinfunction "1_1") (pintype "passive"))
      (node (ref "U$12") (pin "3-09") (pinfunction "3_3-09") (pintype "bidirectional"))
      (node (ref "U$16") (pin "3-09") (pinfunction "3_3-09") (pintype "bidirectional"))
      (node (ref "U$27") (pin "3-09") (pinfunction "3_3-09") (pintype "bidirectional"))
      (node (ref "U$28") (pin "3-09") (pinfunction "3_3-09") (pintype "bidirectional"))
      (node (ref "U$31") (pin "3-09") (pinfunction "3_3-09") (pintype "bidirectional"))
      (node (ref "U$32") (pin "3-09") (pinfunction "3_3-09") (pintype "bidirectional"))
    )
    (net (code "19") (name "5V0") (class "Default")
      (node (ref "C28") (pin "+") (pinfunction "+_+") (pintype "passive"))
      (node (ref "IC12") (pin "P$5") (pinfunction "OUT_P$5") (pintype "bidirectional"))
      (node (ref "JP5") (pin "20") (pinfunction "20_20") (pintype "passive"))
      (node (ref "OLED1") (pin "P$6") (pinfunction "VIN_P$6") (pintype "bidirectional"))
      (node (ref "X2") (pin "1") (pinfunction "1_1") (pintype "passive"))
    )
    (net (code "20") (name "9V0") (class "Default")
      (node (ref "C13") (pin "+") (pinfunction "+_+") (pintype "passive"))
      (node (ref "C14") (pin "1") (pinfunction "1_1") (pintype "passive"))
      (node (ref "C34") (pin "1") (pinfunction "1_1") (pintype "passive"))
      (node (ref "IC11") (pin "P$2") (pinfunction "IN_VCC_P$2") (pintype "bidirectional"))
      (node (ref "IC12") (pin "P$2") (pinfunction "IN_VCC_P$2") (pintype "bidirectional"))
      (node (ref "L5") (pin "2") (pinfunction "2_2") (pintype "passive"))
    )
    (net (code "21") (name "AGND") (class "Default")
      (node (ref "AGND3") (pin "1") (pinfunction "1_1") (pintype "passive"))
      (node (ref "AGND4") (pin "1") (pinfunction "1_1") (pintype "passive"))
      (node (ref "C1") (pin "2") (pinfunction "2_2") (pintype "passive"))
      (node (ref "C10") (pin "2") (pinfunction "2_2") (pintype "passive"))
      (node (ref "C11") (pin "2") (pinfunction "2_2") (pintype "passive"))
      (node (ref "C15") (pin "-") (pinfunction "-_-") (pintype "passive"))
      (node (ref "C16") (pin "+") (pinfunction "+_+") (pintype "passive"))
      (node (ref "C17") (pin "2") (pinfunction "2_2") (pintype "passive"))
      (node (ref "C18") (pin "2") (pinfunction "2_2") (pintype "passive"))
      (node (ref "C2") (pin "2") (pinfunction "2_2") (pintype "passive"))
      (node (ref "C22") (pin "2") (pinfunction "2_2") (pintype "passive"))
      (node (ref "C23") (pin "2") (pinfunction "2_2") (pintype "passive"))
      (node (ref "C24") (pin "2") (pinfunction "2_2") (pintype "passive"))
      (node (ref "C26") (pin "2") (pinfunction "2_2") (pintype "passive"))
      (node (ref "C3") (pin "2") (pinfunction "2_2") (pintype "passive"))
      (node (ref "C30") (pin "-") (pinfunction "-_-") (pintype "passive"))
      (node (ref "C31") (pin "+") (pinfunction "+_+") (pintype "passive"))
      (node (ref "C32") (pin "2") (pinfunction "2_2") (pintype "passive"))
      (node (ref "C35") (pin "2") (pinfunction "2_2") (pintype "passive"))
      (node (ref "C36") (pin "2") (pinfunction "2_2") (pintype "passive"))
      (node (ref "C37") (pin "2") (pinfunction "2_2") (pintype "passive"))
      (node (ref "C38") (pin "2") (pinfunction "2_2") (pintype "passive"))
      (node (ref "C4") (pin "2") (pinfunction "2_2") (pintype "passive"))
      (node (ref "C40") (pin "2") (pinfunction "2_2") (pintype "passive"))
      (node (ref "C41") (pin "1") (pinfunction "1_1") (pintype "passive"))
      (node (ref "C42") (pin "2") (pinfunction "2_2") (pintype "passive"))
      (node (ref "C44") (pin "1") (pinfunction "1_1") (pintype "passive"))
      (node (ref "C45") (pin "2") (pinfunction "2_2") (pintype "passive"))
      (node (ref "C48") (pin "2") (pinfunction "2_2") (pintype "passive"))
      (node (ref "C49") (pin "1") (pinfunction "1_1") (pintype "passive"))
      (node (ref "C5") (pin "1") (pinfunction "1_1") (pintype "passive"))
      (node (ref "C50") (pin "-") (pinfunction "-_-") (pintype "passive"))
      (node (ref "C51") (pin "2") (pinfunction "2_2") (pintype "passive"))
      (node (ref "C52") (pin "1") (pinfunction "1_1") (pintype "passive"))
      (node (ref "C6") (pin "2") (pinfunction "2_2") (pintype "passive"))
      (node (ref "C7") (pin "1") (pinfunction "1_1") (pintype "passive"))
      (node (ref "C8") (pin "2") (pinfunction "2_2") (pintype "passive"))
      (node (ref "C9") (pin "1") (pinfunction "1_1") (pintype "passive"))
      (node (ref "D14") (pin "1") (pinfunction "A_1") (pintype "passive"))
      (node (ref "D15") (pin "1") (pinfunction "A_1") (pintype "passive"))
      (node (ref "D16") (pin "1") (pinfunction "A_1") (pintype "passive"))
      (node (ref "D3") (pin "1") (pinfunction "A_1") (pintype "passive"))
      (node (ref "IC1") (pin "3") (pinfunction "+IN_3") (pintype "input"))
      (node (ref "IC11") (pin "P$6") (pinfunction "OUTGND_P$6") (pintype "bidirectional"))
      (node (ref "IC13") (pin "3") (pinfunction "GND_3") (pintype "bidirectional"))
      (node (ref "IC3") (pin "5") (pinfunction "REF_5") (pintype "passive"))
      (node (ref "IC4") (pin "10") (pinfunction "+IN_10") (pintype "input"))
      (node (ref "IC4") (pin "12") (pinfunction "+IN_12") (pintype "input"))
      (node (ref "J1") (pin "S") (pinfunction "S_S") (pintype "bidirectional"))
      (node (ref "J3") (pin "S") (pinfunction "S_S") (pintype "bidirectional"))
      (node (ref "J4") (pin "S") (pinfunction "S_S") (pintype "bidirectional"))
      (node (ref "J9") (pin "S") (pinfunction "S_S") (pintype "bidirectional"))
      (node (ref "JP13") (pin "3") (pinfunction "3_3") (pintype "passive"))
      (node (ref "JP13") (pin "4") (pinfunction "4_4") (pintype "passive"))
      (node (ref "JP13") (pin "5") (pinfunction "5_5") (pintype "passive"))
      (node (ref "JP13") (pin "6") (pinfunction "6_6") (pintype "passive"))
      (node (ref "JP6") (pin "2") (pinfunction "2_2") (pintype "passive"))
      (node (ref "R10") (pin "1") (pinfunction "1_1") (pintype "passive"))
      (node (ref "R12") (pin "1") (pinfunction "1_1") (pintype "passive"))
      (node (ref "R14") (pin "1") (pinfunction "1_1") (pintype "passive"))
      (node (ref "R17") (pin "1") (pinfunction "1_1") (pintype "passive"))
      (node (ref "R18") (pin "1") (pinfunction "1_1") (pintype "passive"))
      (node (ref "R2") (pin "1") (pinfunction "1_1") (pintype "passive"))
      (node (ref "R26") (pin "2") (pinfunction "2_2") (pintype "passive"))
      (node (ref "R29") (pin "1") (pinfunction "1_1") (pintype "passive"))
      (node (ref "R3") (pin "1") (pinfunction "1_1") (pintype "passive"))
      (node (ref "R30") (pin "1") (pinfunction "1_1") (pintype "passive"))
      (node (ref "R42") (pin "1") (pinfunction "1_1") (pintype "passive"))
      (node (ref "R45") (pin "1") (pinfunction "1_1") (pintype "passive"))
      (node (ref "R63") (pin "1") (pinfunction "1_1") (pintype "passive"))
      (node (ref "R7") (pin "1") (pinfunction "1_1") (pintype "passive"))
      (node (ref "R9") (pin "1") (pinfunction "1_1") (pintype "passive"))
      (node (ref "S12") (pin "1") (pinfunction "S_1") (pintype "passive"))
      (node (ref "T1") (pin "E") (pinfunction "E_E") (pintype "passive"))
      (node (ref "T14") (pin "E") (pinfunction "E_E") (pintype "passive"))
      (node (ref "T2") (pin "E") (pinfunction "E_E") (pintype "passive"))
      (node (ref "T3") (pin "E") (pinfunction "E_E") (pintype "passive"))
      (node (ref "U$12") (pin "1-09") (pinfunction "1_1-09") (pintype "bidirectional"))
      (node (ref "U$14") (pin "2-09") (pinfunction "2_2-09") (pintype "bidirectional"))
      (node (ref "U$16") (pin "1-09") (pinfunction "1_1-09") (pintype "bidirectional"))
      (node (ref "U$27") (pin "1-09") (pinfunction "1_1-09") (pintype "bidirectional"))
      (node (ref "U$28") (pin "1-09") (pinfunction "1_1-09") (pintype "bidirectional"))
      (node (ref "U$31") (pin "1-09") (pinfunction "1_1-09") (pintype "bidirectional"))
      (node (ref "U$32") (pin "1-09") (pinfunction "1_1-09") (pintype "bidirectional"))
      (node (ref "X1") (pin "1") (pinfunction "1_1") (pintype "passive"))
      (node (ref "X1") (pin "G") (pinfunction "G_G") (pintype "passive"))
      (node (ref "X1") (pin "S") (pinfunction "S_S") (pintype "passive"))
    )
    (net (code "22") (name "DGND") (class "Default")
      (node (ref "C13") (pin "-") (pinfunction "-_-") (pintype "passive"))
      (node (ref "C14") (pin "2") (pinfunction "2_2") (pintype "passive"))
      (node (ref "C27") (pin "-") (pinfunction "-_-") (pintype "passive"))
      (node (ref "C28") (pin "-") (pinfunction "-_-") (pintype "passive"))
      (node (ref "C29") (pin "-") (pinfunction "-_-") (pintype "passive"))
      (node (ref "C34") (pin "2") (pinfunction "2_2") (pintype "passive"))
      (node (ref "DGND1") (pin "1") (pinfunction "1_1") (pintype "passive"))
      (node (ref "IC11") (pin "P$1") (pinfunction "IN_GND_P$1") (pintype "bidirectional"))
      (node (ref "IC12") (pin "P$1") (pinfunction "IN_GND_P$1") (pintype "bidirectional"))
      (node (ref "IC12") (pin "P$6") (pinfunction "OUT_GND_P$6") (pintype "bidirectional"))
      (node (ref "J10") (pin "2") (pinfunction "SHEILD_2") (pintype "bidirectional"))
      (node (ref "JP20") (pin "1") (pinfunction "1_1") (pintype "passive"))
      (node (ref "JP5") (pin "19") (pinfunction "19_19") (pintype "passive"))
      (node (ref "LED1") (pin "C") (pinfunction "C_C") (pintype "passive"))
      (node (ref "LED12") (pin "C") (pinfunction "C_C") (pintype "passive"))
      (node (ref "LED13") (pin "C") (pinfunction "C_C") (pintype "passive"))
      (node (ref "LED15") (pin "C") (pinfunction "C_C") (pintype "passive"))
      (node (ref "LED17") (pin "C") (pinfunction "C_C") (pintype "passive"))
      (node (ref "LED2") (pin "C") (pinfunction "C_C") (pintype "passive"))
      (node (ref "LED4") (pin "C") (pinfunction "C_C") (pintype "passive"))
      (node (ref "LED5") (pin "C") (pinfunction "C_C") (pintype "passive"))
      (node (ref "LED6") (pin "C") (pinfunction "C_C") (pintype "passive"))
      (node (ref "LED7") (pin "C") (pinfunction "C_C") (pintype "passive"))
      (node (ref "LED9") (pin "C") (pinfunction "C_C") (pintype "passive"))
      (node (ref "OLED1") (pin "P$4") (pinfunction "GND_P$4") (pintype "bidirectional"))
      (node (ref "U$11") (pin "P1_1") (pinfunction "P$1_P1_1") (pintype "bidirectional"))
      (node (ref "U$11") (pin "P1_2") (pinfunction "P$2_P1_2") (pintype "bidirectional"))
      (node (ref "U$11") (pin "P1_3") (pinfunction "P$3_P1_3") (pintype "bidirectional"))
      (node (ref "U$33") (pin "P1_1") (pinfunction "P$1_P1_1") (pintype "bidirectional"))
      (node (ref "U$33") (pin "P1_2") (pinfunction "P$2_P1_2") (pintype "bidirectional"))
      (node (ref "U$33") (pin "P1_3") (pinfunction "P$3_P1_3") (pintype "bidirectional"))
      (node (ref "U$39") (pin "P1_1") (pinfunction "P$1_P1_1") (pintype "bidirectional"))
      (node (ref "U$39") (pin "P1_2") (pinfunction "P$2_P1_2") (pintype "bidirectional"))
      (node (ref "U$39") (pin "P1_3") (pinfunction "P$3_P1_3") (pintype "bidirectional"))
      (node (ref "U$40") (pin "P1_1") (pinfunction "P$1_P1_1") (pintype "bidirectional"))
      (node (ref "U$40") (pin "P1_2") (pinfunction "P$2_P1_2") (pintype "bidirectional"))
      (node (ref "U$40") (pin "P1_3") (pinfunction "P$3_P1_3") (pintype "bidirectional"))
      (node (ref "U$42") (pin "P1_1") (pinfunction "P$1_P1_1") (pintype "bidirectional"))
      (node (ref "U$42") (pin "P1_2") (pinfunction "P$2_P1_2") (pintype "bidirectional"))
      (node (ref "U$42") (pin "P1_3") (pinfunction "P$3_P1_3") (pintype "bidirectional"))
      (node (ref "U$43") (pin "P1_1") (pinfunction "P$1_P1_1") (pintype "bidirectional"))
      (node (ref "U$43") (pin "P1_2") (pinfunction "P$2_P1_2") (pintype "bidirectional"))
      (node (ref "U$43") (pin "P1_3") (pinfunction "P$3_P1_3") (pintype "bidirectional"))
      (node (ref "U$44") (pin "P1_1") (pinfunction "P$1_P1_1") (pintype "bidirectional"))
      (node (ref "U$44") (pin "P1_2") (pinfunction "P$2_P1_2") (pintype "bidirectional"))
      (node (ref "U$44") (pin "P1_3") (pinfunction "P$3_P1_3") (pintype "bidirectional"))
      (node (ref "U$45") (pin "P1_1") (pinfunction "P$1_P1_1") (pintype "bidirectional"))
      (node (ref "U$45") (pin "P1_2") (pinfunction "P$2_P1_2") (pintype "bidirectional"))
      (node (ref "U$45") (pin "P1_3") (pinfunction "P$3_P1_3") (pintype "bidirectional"))
      (node (ref "U$48") (pin "P1_1") (pinfunction "P$1_P1_1") (pintype "bidirectional"))
      (node (ref "U$48") (pin "P1_2") (pinfunction "P$2_P1_2") (pintype "bidirectional"))
      (node (ref "U$48") (pin "P1_3") (pinfunction "P$3_P1_3") (pintype "bidirectional"))
      (node (ref "U$7") (pin "P1_1") (pinfunction "P$1_P1_1") (pintype "bidirectional"))
      (node (ref "U$7") (pin "P1_2") (pinfunction "P$2_P1_2") (pintype "bidirectional"))
      (node (ref "U$7") (pin "P1_3") (pinfunction "P$3_P1_3") (pintype "bidirectional"))
      (node (ref "X2") (pin "4") (pinfunction "4_4") (pintype "passive"))
    )
    (net (code "23") (name "Net-(C12-Pad+)") (class "Default")
      (node (ref "C12") (pin "+") (pinfunction "+_+") (pintype "passive"))
      (node (ref "C20") (pin "1") (pinfunction "1_1") (pintype "passive"))
      (node (ref "R43") (pin "2") (pinfunction "2_2") (pintype "passive"))
      (node (ref "X1") (pin "2") (pinfunction "2_2") (pintype "passive"))
    )
    (net (code "24") (name "Net-(C19-Pad+)") (class "Default")
      (node (ref "C19") (pin "+") (pinfunction "+_+") (pintype "passive"))
      (node (ref "C21") (pin "2") (pinfunction "2_2") (pintype "passive"))
      (node (ref "R44") (pin "2") (pinfunction "2_2") (pintype "passive"))
      (node (ref "X1") (pin "3") (pinfunction "3_3") (pintype "passive"))
    )
    (net (code "25") (name "Net-(C20-Pad2)") (class "Default")
      (node (ref "C20") (pin "2") (pinfunction "2_2") (pintype "passive"))
      (node (ref "C21") (pin "1") (pinfunction "1_1") (pintype "passive"))
      (node (ref "C22") (pin "1") (pinfunction "1_1") (pintype "passive"))
    )
    (net (code "26") (name "Net-(C33-Pad+)") (class "Default")
      (node (ref "C33") (pin "+") (pinfunction "+_+") (pintype "passive"))
      (node (ref "R19") (pin "2") (pinfunction "2_2") (pintype "passive"))
      (node (ref "R20") (pin "2") (pinfunction "2_2") (pintype "passive"))
      (node (ref "R21") (pin "2") (pinfunction "2_2") (pintype "passive"))
      (node (ref "R33") (pin "2") (pinfunction "2_2") (pintype "passive"))
      (node (ref "R34") (pin "2") (pinfunction "2_2") (pintype "passive"))
      (node (ref "R35") (pin "2") (pinfunction "2_2") (pintype "passive"))
      (node (ref "R36") (pin "2") (pinfunction "2_2") (pintype "passive"))
      (node (ref "R37") (pin "2") (pinfunction "2_2") (pintype "passive"))
      (node (ref "R38") (pin "2") (pinfunction "2_2") (pintype "passive"))
      (node (ref "R5") (pin "2") (pinfunction "2_2") (pintype "passive"))
      (node (ref "R6") (pin "2") (pinfunction "2_2") (pintype "passive"))
      (node (ref "U$1") (pin "1") (pinfunction "1_1") (pintype "bidirectional"))
    )
    (net (code "27") (name "Net-(C46-Pad1)") (class "Default")
      (node (ref "C46") (pin "1") (pinfunction "1_1") (pintype "passive"))
      (node (ref "R28") (pin "2") (pinfunction "2_2") (pintype "passive"))
    )
    (net (code "28") (name "Net-(C46-Pad2)") (class "Default")
      (node (ref "C46") (pin "2") (pinfunction "2_2") (pintype "passive"))
      (node (ref "J3") (pin "R") (pinfunction "R_R") (pintype "bidirectional"))
      (node (ref "R29") (pin "2") (pinfunction "2_2") (pintype "passive"))
    )
    (net (code "29") (name "Net-(C47-Pad1)") (class "Default")
      (node (ref "C47") (pin "1") (pinfunction "1_1") (pintype "passive"))
      (node (ref "R31") (pin "2") (pinfunction "2_2") (pintype "passive"))
    )
    (net (code "30") (name "Net-(C47-Pad2)") (class "Default")
      (node (ref "C47") (pin "2") (pinfunction "2_2") (pintype "passive"))
      (node (ref "J4") (pin "R") (pinfunction "R_R") (pintype "bidirectional"))
      (node (ref "R30") (pin "2") (pinfunction "2_2") (pintype "passive"))
    )
    (net (code "31") (name "Net-(D3-C)") (class "Default")
      (node (ref "D3") (pin "3") (pinfunction "C_3") (pintype "passive"))
      (node (ref "R39") (pin "2") (pinfunction "2_2") (pintype "passive"))
      (node (ref "T14") (pin "B") (pinfunction "B_B") (pintype "passive"))
    )
    (net (code "32") (name "Net-(D11-A)") (class "Default")
      (node (ref "D11") (pin "1") (pinfunction "A_1") (pintype "passive"))
      (node (ref "IC13") (pin "2") (pinfunction "NC_2") (pintype "bidirectional"))
      (node (ref "X1") (pin "T") (pinfunction "T_T") (pintype "passive"))
    )
    (net (code "33") (name "Net-(D14-C)") (class "Default")
      (node (ref "D14") (pin "3") (pinfunction "C_3") (pintype "passive"))
      (node (ref "R41") (pin "2") (pinfunction "2_2") (pintype "passive"))
      (node (ref "T1") (pin "B") (pinfunction "B_B") (pintype "passive"))
    )
    (net (code "34") (name "Net-(D15-C)") (class "Default")
      (node (ref "D15") (pin "3") (pinfunction "C_3") (pintype "passive"))
      (node (ref "R16") (pin "2") (pinfunction "2_2") (pintype "passive"))
      (node (ref "T3") (pin "B") (pinfunction "B_B") (pintype "passive"))
    )
    (net (code "35") (name "Net-(D16-C)") (class "Default")
      (node (ref "D16") (pin "3") (pinfunction "C_3") (pintype "passive"))
      (node (ref "R4") (pin "2") (pinfunction "2_2") (pintype "passive"))
      (node (ref "T2") (pin "B") (pinfunction "B_B") (pintype "passive"))
    )
    (net (code "36") (name "Net-(GPIO-Pad1)") (class "Default")
      (node (ref "GPIO") (pin "1") (pinfunction "1_1") (pintype "passive"))
      (node (ref "JP6") (pin "16") (pinfunction "16_16") (pintype "passive"))
    )
    (net (code "37") (name "Net-(IC1A--IN)") (class "Default")
      (node (ref "IC1") (pin "1") (pinfunction "OUT_1") (pintype "output"))
      (node (ref "IC1") (pin "2") (pinfunction "-IN_2") (pintype "input"))
    )
    (net (code "38") (name "Net-(IC1B-+IN)") (class "Default")
      (node (ref "C45") (pin "1") (pinfunction "1_1") (pintype "passive"))
      (node (ref "IC1") (pin "5") (pinfunction "+IN_5") (pintype "input"))
      (node (ref "J9") (pin "T") (pinfunction "T_T") (pintype "bidirectional"))
      (node (ref "R14") (pin "2") (pinfunction "2_2") (pintype "passive"))
    )
    (net (code "39") (name "Net-(IC1C-+IN)") (class "Default")
      (node (ref "C36") (pin "1") (pinfunction "1_1") (pintype "passive"))
      (node (ref "IC1") (pin "10") (pinfunction "+IN_10") (pintype "input"))
      (node (ref "R63") (pin "2") (pinfunction "2_2") (pintype "passive"))
      (node (ref "U$16") (pin "2-09") (pinfunction "2_2-09") (pintype "bidirectional"))
    )
    (net (code "40") (name "Net-(IC1D-+IN)") (class "Default")
      (node (ref "C10") (pin "1") (pinfunction "1_1") (pintype "passive"))
      (node (ref "IC1") (pin "12") (pinfunction "+IN_12") (pintype "input"))
      (node (ref "R10") (pin "2") (pinfunction "2_2") (pintype "passive"))
      (node (ref "U$12") (pin "2-09") (pinfunction "2_2-09") (pintype "bidirectional"))
    )
    (net (code "41") (name "Net-(IC2A-+IN)") (class "Default")
      (node (ref "C32") (pin "1") (pinfunction "1_1") (pintype "passive"))
      (node (ref "IC2") (pin "3") (pinfunction "+IN_3") (pintype "input"))
      (node (ref "R3") (pin "2") (pinfunction "2_2") (pintype "passive"))
      (node (ref "U$32") (pin "2-09") (pinfunction "2_2-09") (pintype "bidirectional"))
    )
    (net (code "42") (name "Net-(IC2B-+IN)") (class "Default")
      (node (ref "C38") (pin "1") (pinfunction "1_1") (pintype "passive"))
      (node (ref "IC2") (pin "5") (pinfunction "+IN_5") (pintype "input"))
      (node (ref "R17") (pin "2") (pinfunction "2_2") (pintype "passive"))
      (node (ref "U$28") (pin "2-09") (pinfunction "2_2-09") (pintype "bidirectional"))
    )
    (net (code "43") (name "Net-(IC2C-+IN)") (class "Default")
      (node (ref "C42") (pin "1") (pinfunction "1_1") (pintype "passive"))
      (node (ref "IC2") (pin "10") (pinfunction "+IN_10") (pintype "input"))
      (node (ref "R18") (pin "2") (pinfunction "2_2") (pintype "passive"))
      (node (ref "U$27") (pin "2-09") (pinfunction "2_2-09") (pintype "bidirectional"))
    )
    (net (code "44") (name "Net-(IC2D-+IN)") (class "Default")
      (node (ref "C11") (pin "1") (pinfunction "1_1") (pintype "passive"))
      (node (ref "IC2") (pin "12") (pinfunction "+IN_12") (pintype "input"))
      (node (ref "R2") (pin "2") (pinfunction "2_2") (pintype "passive"))
      (node (ref "U$31") (pin "2-09") (pinfunction "2_2-09") (pintype "bidirectional"))
    )
    (net (code "45") (name "Net-(IC3-+IN)") (class "Default")
      (node (ref "C19") (pin "-") (pinfunction "-_-") (pintype "passive"))
      (node (ref "C24") (pin "1") (pinfunction "1_1") (pintype "passive"))
      (node (ref "C25") (pin "2") (pinfunction "2_2") (pintype "passive"))
      (node (ref "IC3") (pin "3") (pinfunction "+IN_3") (pintype "input"))
      (node (ref "R12") (pin "2") (pinfunction "2_2") (pintype "passive"))
    )
    (net (code "46") (name "Net-(IC3--IN)") (class "Default")
      (node (ref "C12") (pin "-") (pinfunction "-_-") (pintype "passive"))
      (node (ref "C23") (pin "1") (pinfunction "1_1") (pintype "passive"))
      (node (ref "C25") (pin "1") (pinfunction "1_1") (pintype "passive"))
      (node (ref "IC3") (pin "2") (pinfunction "-IN_2") (pintype "input"))
      (node (ref "R9") (pin "2") (pinfunction "2_2") (pintype "passive"))
    )
    (net (code "47") (name "Net-(IC3-RG1)") (class "Default")
      (node (ref "IC3") (pin "1") (pinfunction "RG1_1") (pintype "passive"))
      (node (ref "R13") (pin "2") (pinfunction "2_2") (pintype "passive"))
    )
    (net (code "48") (name "Net-(IC3-RG2)") (class "Default")
      (node (ref "C33") (pin "-") (pinfunction "-_-") (pintype "passive"))
      (node (ref "IC3") (pin "8") (pinfunction "RG2_8") (pintype "passive"))
    )
    (net (code "49") (name "Net-(IC4A--IN)") (class "Default")
      (node (ref "IC4") (pin "1") (pinfunction "OUT_1") (pintype "output"))
      (node (ref "IC4") (pin "2") (pinfunction "-IN_2") (pintype "input"))
      (node (ref "R46") (pin "2") (pinfunction "2_2") (pintype "passive"))
    )
    (net (code "50") (name "Net-(IC4B--IN)") (class "Default")
      (node (ref "IC4") (pin "6") (pinfunction "-IN_6") (pintype "input"))
      (node (ref "IC4") (pin "7") (pinfunction "OUT_7") (pintype "output"))
      (node (ref "R47") (pin "2") (pinfunction "2_2") (pintype "passive"))
    )
    (net (code "51") (name "Net-(IC4C--IN)") (class "Default")
      (node (ref "IC4") (pin "9") (pinfunction "-IN_9") (pintype "input"))
      (node (ref "R48") (pin "1") (pinfunction "1_1") (pintype "passive"))
      (node (ref "R49") (pin "1") (pinfunction "1_1") (pintype "passive"))
      (node (ref "R50") (pin "2") (pinfunction "2_2") (pintype "passive"))
    )
    (net (code "52") (name "Net-(IC4C-OUT)") (class "Default")
      (node (ref "IC4") (pin "8") (pinfunction "OUT_8") (pintype "output"))
      (node (ref "R50") (pin "1") (pinfunction "1_1") (pintype "passive"))
      (node (ref "R51") (pin "2") (pinfunction "2_2") (pintype "passive"))
    )
    (net (code "53") (name "Net-(IC4D--IN)") (class "Default")
      (node (ref "IC4") (pin "13") (pinfunction "-IN_13") (pintype "input"))
      (node (ref "R51") (pin "1") (pinfunction "1_1") (pintype "passive"))
      (node (ref "R52") (pin "2") (pinfunction "2_2") (pintype "passive"))
    )
    (net (code "54") (name "Net-(IC4D-OUT)") (class "Default")
      (node (ref "CH1_OUT") (pin "1") (pinfunction "1_1") (pintype "passive"))
      (node (ref "IC4") (pin "14") (pinfunction "OUT_14") (pintype "output"))
      (node (ref "IC5") (pin "5") (pinfunction "+IN_5") (pintype "input"))
      (node (ref "R52") (pin "1") (pinfunction "1_1") (pintype "passive"))
    )
    (net (code "55") (name "Net-(IC5A--IN)") (class "Default")
      (node (ref "IC5") (pin "2") (pinfunction "-IN_2") (pintype "input"))
      (node (ref "R7") (pin "2") (pinfunction "2_2") (pintype "passive"))
      (node (ref "R8") (pin "2") (pinfunction "2_2") (pintype "passive"))
    )
    (net (code "56") (name "Net-(IC5A-OUT)") (class "Default")
      (node (ref "IC5") (pin "1") (pinfunction "OUT_1") (pintype "output"))
      (node (ref "R27") (pin "2") (pinfunction "2_2") (pintype "passive"))
      (node (ref "R8") (pin "1") (pinfunction "1_1") (pintype "passive"))
    )
    (net (code "57") (name "Net-(IC5B--IN)") (class "Default")
      (node (ref "IC5") (pin "6") (pinfunction "-IN_6") (pintype "input"))
      (node (ref "R22") (pin "2") (pinfunction "2_2") (pintype "passive"))
      (node (ref "R26") (pin "1") (pinfunction "1_1") (pintype "passive"))
    )
    (net (code "58") (name "Net-(IC5B-OUT)") (class "Default")
      (node (ref "IC5") (pin "7") (pinfunction "OUT_7") (pintype "output"))
      (node (ref "R22") (pin "1") (pinfunction "1_1") (pintype "passive"))
      (node (ref "R32") (pin "2") (pinfunction "2_2") (pintype "passive"))
    )
    (net (code "59") (name "Net-(IC11-OUT+)") (class "Default")
      (node (ref "IC11") (pin "P$5") (pinfunction "OUT+_P$5") (pintype "bidirectional"))
      (node (ref "L2") (pin "1") (pinfunction "1_1") (pintype "passive"))
    )
    (net (code "60") (name "Net-(IC11-OUT-)") (class "Default")
      (node (ref "IC11") (pin "P$7") (pinfunction "OUT-_P$7") (pintype "bidirectional"))
      (node (ref "L1") (pin "1") (pinfunction "1_1") (pintype "passive"))
    )
    (net (code "61") (name "Net-(IC12-CS)") (class "Default")
      (node (ref "C29") (pin "+") (pinfunction "+_+") (pintype "passive"))
      (node (ref "IC12") (pin "P$7") (pinfunction "CS_P$7") (pintype "bidirectional"))
    )
    (net (code "62") (name "Net-(IC13-IN)") (class "Default")
      (node (ref "IC13") (pin "6") (pinfunction "IN_6") (pintype "bidirectional"))
      (node (ref "R23") (pin "1") (pinfunction "1_1") (pintype "passive"))
      (node (ref "X1") (pin "SS") (pinfunction "SS_SS") (pintype "passive"))
    )
    (net (code "63") (name "Net-(J3-PadT)") (class "Default")
      (node (ref "J3") (pin "T") (pinfunction "T_T") (pintype "bidirectional"))
      (node (ref "R27") (pin "1") (pinfunction "1_1") (pintype "passive"))
      (node (ref "R28") (pin "1") (pinfunction "1_1") (pintype "passive"))
      (node (ref "R39") (pin "1") (pinfunction "1_1") (pintype "passive"))
    )
    (net (code "64") (name "Net-(J4-PadT)") (class "Default")
      (node (ref "J4") (pin "T") (pinfunction "T_T") (pintype "bidirectional"))
      (node (ref "R31") (pin "1") (pinfunction "1_1") (pintype "passive"))
      (node (ref "R32") (pin "1") (pinfunction "1_1") (pintype "passive"))
      (node (ref "R41") (pin "1") (pinfunction "1_1") (pintype "passive"))
    )
    (net (code "65") (name "Net-(J10-TIP)") (class "Default")
      (node (ref "C27") (pin "+") (pinfunction "+_+") (pintype "passive"))
      (node (ref "J10") (pin "1") (pinfunction "TIP_1") (pintype "bidirectional"))
      (node (ref "L5") (pin "1") (pinfunction "1_1") (pintype "passive"))
    )
    (net (code "66") (name "Net-(JP5-Pad9)") (class "Default")
      (node (ref "JP5") (pin "9") (pinfunction "9_9") (pintype "passive"))
      (node (ref "R11") (pin "1") (pinfunction "1_1") (pintype "passive"))
    )
    (net (code "67") (name "Net-(JP5-Pad11)") (class "Default")
      (node (ref "JP5") (pin "11") (pinfunction "11_11") (pintype "passive"))
      (node (ref "R55") (pin "1") (pinfunction "1_1") (pintype "passive"))
    )
    (net (code "68") (name "Net-(JP5-Pad12)") (class "Default")
      (node (ref "JP5") (pin "12") (pinfunction "12_12") (pintype "passive"))
      (node (ref "R54") (pin "1") (pinfunction "1_1") (pintype "passive"))
    )
    (net (code "69") (name "Net-(JP5-Pad13)") (class "Default")
      (node (ref "JP5") (pin "13") (pinfunction "13_13") (pintype "passive"))
      (node (ref "R56") (pin "1") (pinfunction "1_1") (pintype "passive"))
    )
    (net (code "70") (name "Net-(JP5-Pad14)") (class "Default")
      (node (ref "JP5") (pin "14") (pinfunction "14_14") (pintype "passive"))
      (node (ref "R53") (pin "1") (pinfunction "1_1") (pintype "passive"))
    )
    (net (code "71") (name "Net-(JP5-Pad15)") (class "Default")
      (node (ref "JP5") (pin "15") (pinfunction "15_15") (pintype "passive"))
      (node (ref "R57") (pin "1") (pinfunction "1_1") (pintype "passive"))
    )
    (net (code "72") (name "Net-(JP6-Pad8)") (class "Default")
      (node (ref "JP6") (pin "8") (pinfunction "8_8") (pintype "passive"))
      (node (ref "R62") (pin "1") (pinfunction "1_1") (pintype "passive"))
    )
    (net (code "73") (name "Net-(JP6-Pad10)") (class "Default")
      (node (ref "JP6") (pin "10") (pinfunction "10_10") (pintype "passive"))
      (node (ref "R61") (pin "1") (pinfunction "1_1") (pintype "passive"))
    )
    (net (code "74") (name "Net-(JP6-Pad12)") (class "Default")
      (node (ref "JP6") (pin "12") (pinfunction "12_12") (pintype "passive"))
      (node (ref "R60") (pin "1") (pinfunction "1_1") (pintype "passive"))
    )
    (net (code "75") (name "Net-(JP6-Pad14)") (class "Default")
      (node (ref "JP6") (pin "14") (pinfunction "14_14") (pintype "passive"))
      (node (ref "R59") (pin "1") (pinfunction "1_1") (pintype "passive"))
    )
    (net (code "76") (name "Net-(JP6-Pad17)") (class "Default")
      (node (ref "JP6") (pin "17") (pinfunction "17_17") (pintype "passive"))
      (node (ref "R58") (pin "1") (pinfunction "1_1") (pintype "passive"))
    )
    (net (code "77") (name "Net-(LED1-PadA)") (class "Default")
      (node (ref "LED1") (pin "A") (pinfunction "A_A") (pintype "passive"))
      (node (ref "R11") (pin "2") (pinfunction "2_2") (pintype "passive"))
    )
    (net (code "78") (name "Net-(LED2-PadA)") (class "Default")
      (node (ref "LED2") (pin "A") (pinfunction "A_A") (pintype "passive"))
      (node (ref "R53") (pin "2") (pinfunction "2_2") (pintype "passive"))
    )
    (net (code "79") (name "Net-(LED4-PadA)") (class "Default")
      (node (ref "LED4") (pin "A") (pinfunction "A_A") (pintype "passive"))
      (node (ref "R54") (pin "2") (pinfunction "2_2") (pintype "passive"))
    )
    (net (code "80") (name "Net-(LED5-PadA)") (class "Default")
      (node (ref "LED5") (pin "A") (pinfunction "A_A") (pintype "passive"))
      (node (ref "R55") (pin "2") (pinfunction "2_2") (pintype "passive"))
    )
    (net (code "81") (name "Net-(LED6-PadA)") (class "Default")
      (node (ref "LED6") (pin "A") (pinfunction "A_A") (pintype "passive"))
      (node (ref "R56") (pin "2") (pinfunction "2_2") (pintype "passive"))
    )
    (net (code "82") (name "Net-(LED7-PadA)") (class "Default")
      (node (ref "LED7") (pin "A") (pinfunction "A_A") (pintype "passive"))
      (node (ref "R57") (pin "2") (pinfunction "2_2") (pintype "passive"))
    )
    (net (code "83") (name "Net-(LED8-PadC)") (class "Default")
      (node (ref "LED8") (pin "C") (pinfunction "C_C") (pintype "passive"))
      (node (ref "R45") (pin "2") (pinfunction "2_2") (pintype "passive"))
    )
    (net (code "84") (name "Net-(LED9-PadA)") (class "Default")
      (node (ref "LED9") (pin "A") (pinfunction "A_A") (pintype "passive"))
      (node (ref "R58") (pin "2") (pinfunction "2_2") (pintype "passive"))
    )
    (net (code "85") (name "Net-(LED10-PadA)") (class "Default")
      (node (ref "LED10") (pin "A") (pinfunction "A_A") (pintype "passive"))
      (node (ref "R1") (pin "2") (pinfunction "2_2") (pintype "passive"))
    )
    (net (code "86") (name "Net-(LED10-PadC)") (class "Default")
      (node (ref "LED10") (pin "C") (pinfunction "C_C") (pintype "passive"))
      (node (ref "T2") (pin "C") (pinfunction "C_C") (pintype "passive"))
    )
    (net (code "87") (name "Net-(LED11-PadA)") (class "Default")
      (node (ref "LED11") (pin "A") (pinfunction "A_A") (pintype "passive"))
      (node (ref "R15") (pin "2") (pinfunction "2_2") (pintype "passive"))
    )
    (net (code "88") (name "Net-(LED11-PadC)") (class "Default")
      (node (ref "LED11") (pin "C") (pinfunction "C_C") (pintype "passive"))
      (node (ref "T3") (pin "C") (pinfunction "C_C") (pintype "passive"))
    )
    (net (code "89") (name "Net-(LED12-PadA)") (class "Default")
      (node (ref "LED12") (pin "A") (pinfunction "A_A") (pintype "passive"))
      (node (ref "R59") (pin "2") (pinfunction "2_2") (pintype "passive"))
    )
    (net (code "90") (name "Net-(LED13-PadA)") (class "Default")
      (node (ref "LED13") (pin "A") (pinfunction "A_A") (pintype "passive"))
      (node (ref "R60") (pin "2") (pinfunction "2_2") (pintype "passive"))
    )
    (net (code "91") (name "Net-(LED14-PadA)") (class "Default")
      (node (ref "LED14") (pin "A") (pinfunction "A_A") (pintype "passive"))
      (node (ref "R40") (pin "2") (pinfunction "2_2") (pintype "passive"))
    )
    (net (code "92") (name "Net-(LED14-PadC)") (class "Default")
      (node (ref "LED14") (pin "C") (pinfunction "C_C") (pintype "passive"))
      (node (ref "T1") (pin "C") (pinfunction "C_C") (pintype "passive"))
    )
    (net (code "93") (name "Net-(LED15-PadA)") (class "Default")
      (node (ref "LED15") (pin "A") (pinfunction "A_A") (pintype "passive"))
      (node (ref "R61") (pin "2") (pinfunction "2_2") (pintype "passive"))
    )
    (net (code "94") (name "Net-(LED16-PadA)") (class "Default")
      (node (ref "LED16") (pin "A") (pinfunction "A_A") (pintype "passive"))
      (node (ref "R65") (pin "2") (pinfunction "2_2") (pintype "passive"))
    )
    (net (code "95") (name "Net-(LED16-PadC)") (class "Default")
      (node (ref "LED16") (pin "C") (pinfunction "C_C") (pintype "passive"))
      (node (ref "T14") (pin "C") (pinfunction "C_C") (pintype "passive"))
    )
    (net (code "96") (name "Net-(LED17-PadA)") (class "Default")
      (node (ref "LED17") (pin "A") (pinfunction "A_A") (pintype "passive"))
      (node (ref "R62") (pin "2") (pinfunction "2_2") (pintype "passive"))
    )
    (net (code "97") (name "Net-(OLED1-RST)") (class "Default")
      (node (ref "JP5") (pin "16") (pinfunction "16_16") (pintype "passive"))
      (node (ref "OLED1") (pin "P$3") (pinfunction "RST_P$3") (pintype "bidirectional"))
    )
    (net (code "98") (name "Net-(OLED1-SCL)") (class "Default")
      (node (ref "JP5") (pin "7") (pinfunction "7_7") (pintype "passive"))
      (node (ref "OLED1") (pin "P$2") (pinfunction "SCL_P$2") (pintype "bidirectional"))
      (node (ref "R24") (pin "2") (pinfunction "2_2") (pintype "passive"))
    )
    (net (code "99") (name "Net-(OLED1-SDA)") (class "Default")
      (node (ref "JP5") (pin "10") (pinfunction "10_10") (pintype "passive"))
      (node (ref "OLED1") (pin "P$1") (pinfunction "SDA_P$1") (pintype "bidirectional"))
      (node (ref "R25") (pin "2") (pinfunction "2_2") (pintype "passive"))
    )
    (net (code "100") (name "Net-(R5-Pad1)") (class "Default")
      (node (ref "R5") (pin "1") (pinfunction "1_1") (pintype "passive"))
      (node (ref "U$1") (pin "8") (pinfunction "8_8") (pintype "bidirectional"))
    )
    (net (code "101") (name "Net-(R6-Pad1)") (class "Default")
      (node (ref "R6") (pin "1") (pinfunction "1_1") (pintype "passive"))
      (node (ref "U$1") (pin "9") (pinfunction "9_9") (pintype "bidirectional"))
    )
    (net (code "102") (name "Net-(R13-Pad1)") (class "Default")
      (node (ref "R13") (pin "1") (pinfunction "1_1") (pintype "passive"))
      (node (ref "U$1") (pin "C") (pinfunction "C_C") (pintype "bidirectional"))
    )
    (net (code "103") (name "Net-(R19-Pad1)") (class "Default")
      (node (ref "R19") (pin "1") (pinfunction "1_1") (pintype "passive"))
      (node (ref "U$1") (pin "10") (pinfunction "10_10") (pintype "bidirectional"))
    )
    (net (code "104") (name "Net-(R20-Pad1)") (class "Default")
      (node (ref "R20") (pin "1") (pinfunction "1_1") (pintype "passive"))
      (node (ref "U$1") (pin "11") (pinfunction "11_11") (pintype "bidirectional"))
    )
    (net (code "105") (name "Net-(R21-Pad1)") (class "Default")
      (node (ref "R21") (pin "1") (pinfunction "1_1") (pintype "passive"))
      (node (ref "U$1") (pin "12") (pinfunction "12_12") (pintype "bidirectional"))
    )
    (net (code "106") (name "Net-(R33-Pad1)") (class "Default")
      (node (ref "R33") (pin "1") (pinfunction "1_1") (pintype "passive"))
      (node (ref "U$1") (pin "2") (pinfunction "2_2") (pintype "bidirectional"))
    )
    (net (code "107") (name "Net-(R34-Pad1)") (class "Default")
      (node (ref "R34") (pin "1") (pinfunction "1_1") (pintype "passive"))
      (node (ref "U$1") (pin "3") (pinfunction "3_3") (pintype "bidirectional"))
    )
    (net (code "108") (name "Net-(R35-Pad1)") (class "Default")
      (node (ref "R35") (pin "1") (pinfunction "1_1") (pintype "passive"))
      (node (ref "U$1") (pin "4") (pinfunction "4_4") (pintype "bidirectional"))
    )
    (net (code "109") (name "Net-(R36-Pad1)") (class "Default")
      (node (ref "R36") (pin "1") (pinfunction "1_1") (pintype "passive"))
      (node (ref "U$1") (pin "5") (pinfunction "5_5") (pintype "bidirectional"))
    )
    (net (code "110") (name "Net-(R37-Pad1)") (class "Default")
      (node (ref "R37") (pin "1") (pinfunction "1_1") (pintype "passive"))
      (node (ref "U$1") (pin "6") (pinfunction "6_6") (pintype "bidirectional"))
    )
    (net (code "111") (name "Net-(R38-Pad1)") (class "Default")
      (node (ref "R38") (pin "1") (pinfunction "1_1") (pintype "passive"))
      (node (ref "U$1") (pin "7") (pinfunction "7_7") (pintype "bidirectional"))
    )
    (net (code "112") (name "Net-(S12A-P)") (class "Default")
      (node (ref "LED8") (pin "A") (pinfunction "A_A") (pintype "passive"))
      (node (ref "S12") (pin "2") (pinfunction "P_2") (pintype "passive"))
    )
    (net (code "113") (name "Net-(S12B-P)") (class "Default")
      (node (ref "R43") (pin "1") (pinfunction "1_1") (pintype "passive"))
      (node (ref "R44") (pin "1") (pinfunction "1_1") (pintype "passive"))
      (node (ref "S12") (pin "5") (pinfunction "P_5") (pintype "passive"))
    )
    (net (code "114") (name "Net-(S12B-S)") (class "Default")
      (node (ref "R42") (pin "2") (pinfunction "2_2") (pintype "passive"))
      (node (ref "S12") (pin "4") (pinfunction "S_4") (pintype "passive"))
    )
    (net (code "115") (name "Net-(U$7-P$4)") (class "Default")
      (node (ref "JP5") (pin "3") (pinfunction "3_3") (pintype "passive"))
      (node (ref "U$7") (pin "P2_1") (pinfunction "P$4_P2_1") (pintype "bidirectional"))
      (node (ref "U$7") (pin "P2_2") (pinfunction "P$5_P2_2") (pintype "bidirectional"))
      (node (ref "U$7") (pin "P2_3") (pinfunction "P$6_P2_3") (pintype "bidirectional"))
    )
    (net (code "116") (name "Net-(U$11-P$4)") (class "Default")
      (node (ref "JP5") (pin "5") (pinfunction "5_5") (pintype "passive"))
      (node (ref "U$11") (pin "P2_1") (pinfunction "P$4_P2_1") (pintype "bidirectional"))
      (node (ref "U$11") (pin "P2_2") (pinfunction "P$5_P2_2") (pintype "bidirectional"))
      (node (ref "U$11") (pin "P2_3") (pinfunction "P$6_P2_3") (pintype "bidirectional"))
    )
    (net (code "117") (name "Net-(U$14-1)") (class "Default")
      (node (ref "R47") (pin "1") (pinfunction "1_1") (pintype "passive"))
      (node (ref "R49") (pin "2") (pinfunction "2_2") (pintype "passive"))
      (node (ref "U$14") (pin "1-09") (pinfunction "1_1-09") (pintype "bidirectional"))
    )
    (net (code "118") (name "Net-(U$14-3)") (class "Default")
      (node (ref "R46") (pin "1") (pinfunction "1_1") (pintype "passive"))
      (node (ref "R48") (pin "2") (pinfunction "2_2") (pintype "passive"))
      (node (ref "U$14") (pin "3-09") (pinfunction "3_3-09") (pintype "bidirectional"))
    )
    (net (code "119") (name "Net-(U$33-P$4)") (class "Default")
      (node (ref "JP5") (pin "6") (pinfunction "6_6") (pintype "passive"))
      (node (ref "U$33") (pin "P2_1") (pinfunction "P$4_P2_1") (pintype "bidirectional"))
      (node (ref "U$33") (pin "P2_2") (pinfunction "P$5_P2_2") (pintype "bidirectional"))
      (node (ref "U$33") (pin "P2_3") (pinfunction "P$6_P2_3") (pintype "bidirectional"))
    )
    (net (code "120") (name "Net-(U$39-P$4)") (class "Default")
      (node (ref "JP5") (pin "4") (pinfunction "4_4") (pintype "passive"))
      (node (ref "U$39") (pin "P2_1") (pinfunction "P$4_P2_1") (pintype "bidirectional"))
      (node (ref "U$39") (pin "P2_2") (pinfunction "P$5_P2_2") (pintype "bidirectional"))
      (node (ref "U$39") (pin "P2_3") (pinfunction "P$6_P2_3") (pintype "bidirectional"))
    )
    (net (code "121") (name "Net-(U$40-P$4)") (class "Default")
      (node (ref "JP5") (pin "8") (pinfunction "8_8") (pintype "passive"))
      (node (ref "U$40") (pin "P2_1") (pinfunction "P$4_P2_1") (pintype "bidirectional"))
      (node (ref "U$40") (pin "P2_2") (pinfunction "P$5_P2_2") (pintype "bidirectional"))
      (node (ref "U$40") (pin "P2_3") (pinfunction "P$6_P2_3") (pintype "bidirectional"))
    )
    (net (code "122") (name "Net-(U$42-P$4)") (class "Default")
      (node (ref "JP6") (pin "13") (pinfunction "13_13") (pintype "passive"))
      (node (ref "U$42") (pin "P2_1") (pinfunction "P$4_P2_1") (pintype "bidirectional"))
      (node (ref "U$42") (pin "P2_2") (pinfunction "P$5_P2_2") (pintype "bidirectional"))
      (node (ref "U$42") (pin "P2_3") (pinfunction "P$6_P2_3") (pintype "bidirectional"))
    )
    (net (code "123") (name "Net-(U$43-P$4)") (class "Default")
      (node (ref "JP6") (pin "15") (pinfunction "15_15") (pintype "passive"))
      (node (ref "U$43") (pin "P2_1") (pinfunction "P$4_P2_1") (pintype "bidirectional"))
      (node (ref "U$43") (pin "P2_2") (pinfunction "P$5_P2_2") (pintype "bidirectional"))
      (node (ref "U$43") (pin "P2_3") (pinfunction "P$6_P2_3") (pintype "bidirectional"))
    )
    (net (code "124") (name "Net-(U$44-P$4)") (class "Default")
      (node (ref "JP6") (pin "20") (pinfunction "20_20") (pintype "passive"))
      (node (ref "U$44") (pin "P2_1") (pinfunction "P$4_P2_1") (pintype "bidirectional"))
      (node (ref "U$44") (pin "P2_2") (pinfunction "P$5_P2_2") (pintype "bidirectional"))
      (node (ref "U$44") (pin "P2_3") (pinfunction "P$6_P2_3") (pintype "bidirectional"))
    )
    (net (code "125") (name "Net-(U$45-P$4)") (class "Default")
      (node (ref "JP6") (pin "19") (pinfunction "19_19") (pintype "passive"))
      (node (ref "U$45") (pin "P2_1") (pinfunction "P$4_P2_1") (pintype "bidirectional"))
      (node (ref "U$45") (pin "P2_2") (pinfunction "P$5_P2_2") (pintype "bidirectional"))
      (node (ref "U$45") (pin "P2_3") (pinfunction "P$6_P2_3") (pintype "bidirectional"))
    )
    (net (code "126") (name "Net-(U$48-P$4)") (class "Default")
      (node (ref "JP6") (pin "18") (pinfunction "18_18") (pintype "passive"))
      (node (ref "U$48") (pin "P2_1") (pinfunction "P$4_P2_1") (pintype "bidirectional"))
      (node (ref "U$48") (pin "P2_2") (pinfunction "P$5_P2_2") (pintype "bidirectional"))
      (node (ref "U$48") (pin "P2_3") (pinfunction "P$6_P2_3") (pintype "bidirectional"))
    )
    (net (code "127") (name "unconnected-(IC11-CTRL-PadP$3)") (class "Default")
      (node (ref "IC11") (pin "P$3") (pinfunction "CTRL_P$3") (pintype "bidirectional"))
    )
    (net (code "128") (name "unconnected-(IC12-CTL-PadP$3)") (class "Default")
      (node (ref "IC12") (pin "P$3") (pinfunction "CTL_P$3") (pintype "bidirectional"))
    )
    (net (code "129") (name "unconnected-(IC13-NOCON-Pad5)") (class "Default")
      (node (ref "IC13") (pin "5") (pinfunction "NOCON_5") (pintype "bidirectional"))
    )
    (net (code "130") (name "unconnected-(J1-PadR)") (class "Default")
      (node (ref "J1") (pin "R") (pinfunction "R_R") (pintype "bidirectional"))
    )
    (net (code "131") (name "unconnected-(J1-PadRN)") (class "Default")
      (node (ref "J1") (pin "RN") (pinfunction "RN_RN") (pintype "bidirectional"))
    )
    (net (code "132") (name "unconnected-(J1-PadSN)") (class "Default")
      (node (ref "J1") (pin "SN") (pinfunction "SN_SN") (pintype "bidirectional"))
    )
    (net (code "133") (name "unconnected-(J1-PadTN)") (class "Default")
      (node (ref "J1") (pin "TN") (pinfunction "TN_TN") (pintype "bidirectional"))
    )
    (net (code "134") (name "unconnected-(J3-PadRN)") (class "Default")
      (node (ref "J3") (pin "RN") (pinfunction "RN_RN") (pintype "bidirectional"))
    )
    (net (code "135") (name "unconnected-(J3-PadSN)") (class "Default")
      (node (ref "J3") (pin "SN") (pinfunction "SN_SN") (pintype "bidirectional"))
    )
    (net (code "136") (name "unconnected-(J3-PadTN)") (class "Default")
      (node (ref "J3") (pin "TN") (pinfunction "TN_TN") (pintype "bidirectional"))
    )
    (net (code "137") (name "unconnected-(J4-PadRN)") (class "Default")
      (node (ref "J4") (pin "RN") (pinfunction "RN_RN") (pintype "bidirectional"))
    )
    (net (code "138") (name "unconnected-(J4-PadSN)") (class "Default")
      (node (ref "J4") (pin "SN") (pinfunction "SN_SN") (pintype "bidirectional"))
    )
    (net (code "139") (name "unconnected-(J4-PadTN)") (class "Default")
      (node (ref "J4") (pin "TN") (pinfunction "TN_TN") (pintype "bidirectional"))
    )
    (net (code "140") (name "unconnected-(J9-PadRN)") (class "Default")
      (node (ref "J9") (pin "RN") (pinfunction "RN_RN") (pintype "bidirectional"))
    )
    (net (code "141") (name "unconnected-(J9-PadSN)") (class "Default")
      (node (ref "J9") (pin "SN") (pinfunction "SN_SN") (pintype "bidirectional"))
    )
    (net (code "142") (name "unconnected-(J9-PadTN)") (class "Default")
      (node (ref "J9") (pin "TN") (pinfunction "TN_TN") (pintype "bidirectional"))
    )
    (net (code "143") (name "unconnected-(J10-SWITCH-Pad3)") (class "Default")
      (node (ref "J10") (pin "3") (pinfunction "SWITCH_3") (pintype "bidirectional"))
    )
    (net (code "144") (name "unconnected-(JP5-Pad1)") (class "Default")
      (node (ref "JP5") (pin "1") (pinfunction "1_1") (pintype "passive"))
    )
    (net (code "145") (name "unconnected-(JP5-Pad2)") (class "Default")
      (node (ref "JP5") (pin "2") (pinfunction "2_2") (pintype "passive"))
    )
    (net (code "146") (name "unconnected-(X1-PadR)") (class "Default")
      (node (ref "X1") (pin "R") (pinfunction "R_R") (pintype "passive"))
    )
    (net (code "147") (name "unconnected-(X1-PadRS)") (class "Default")
      (node (ref "X1") (pin "RS") (pinfunction "RS_RS") (pintype "passive"))
    )
    (net (code "148") (name "unconnected-(X1-PadTS)") (class "Default")
      (node (ref "X1") (pin "TS") (pinfunction "TS_TS") (pintype "passive"))
    )
  )
)
